# ebox.net
KiCad netlist of a schematic drawn in EAGLE
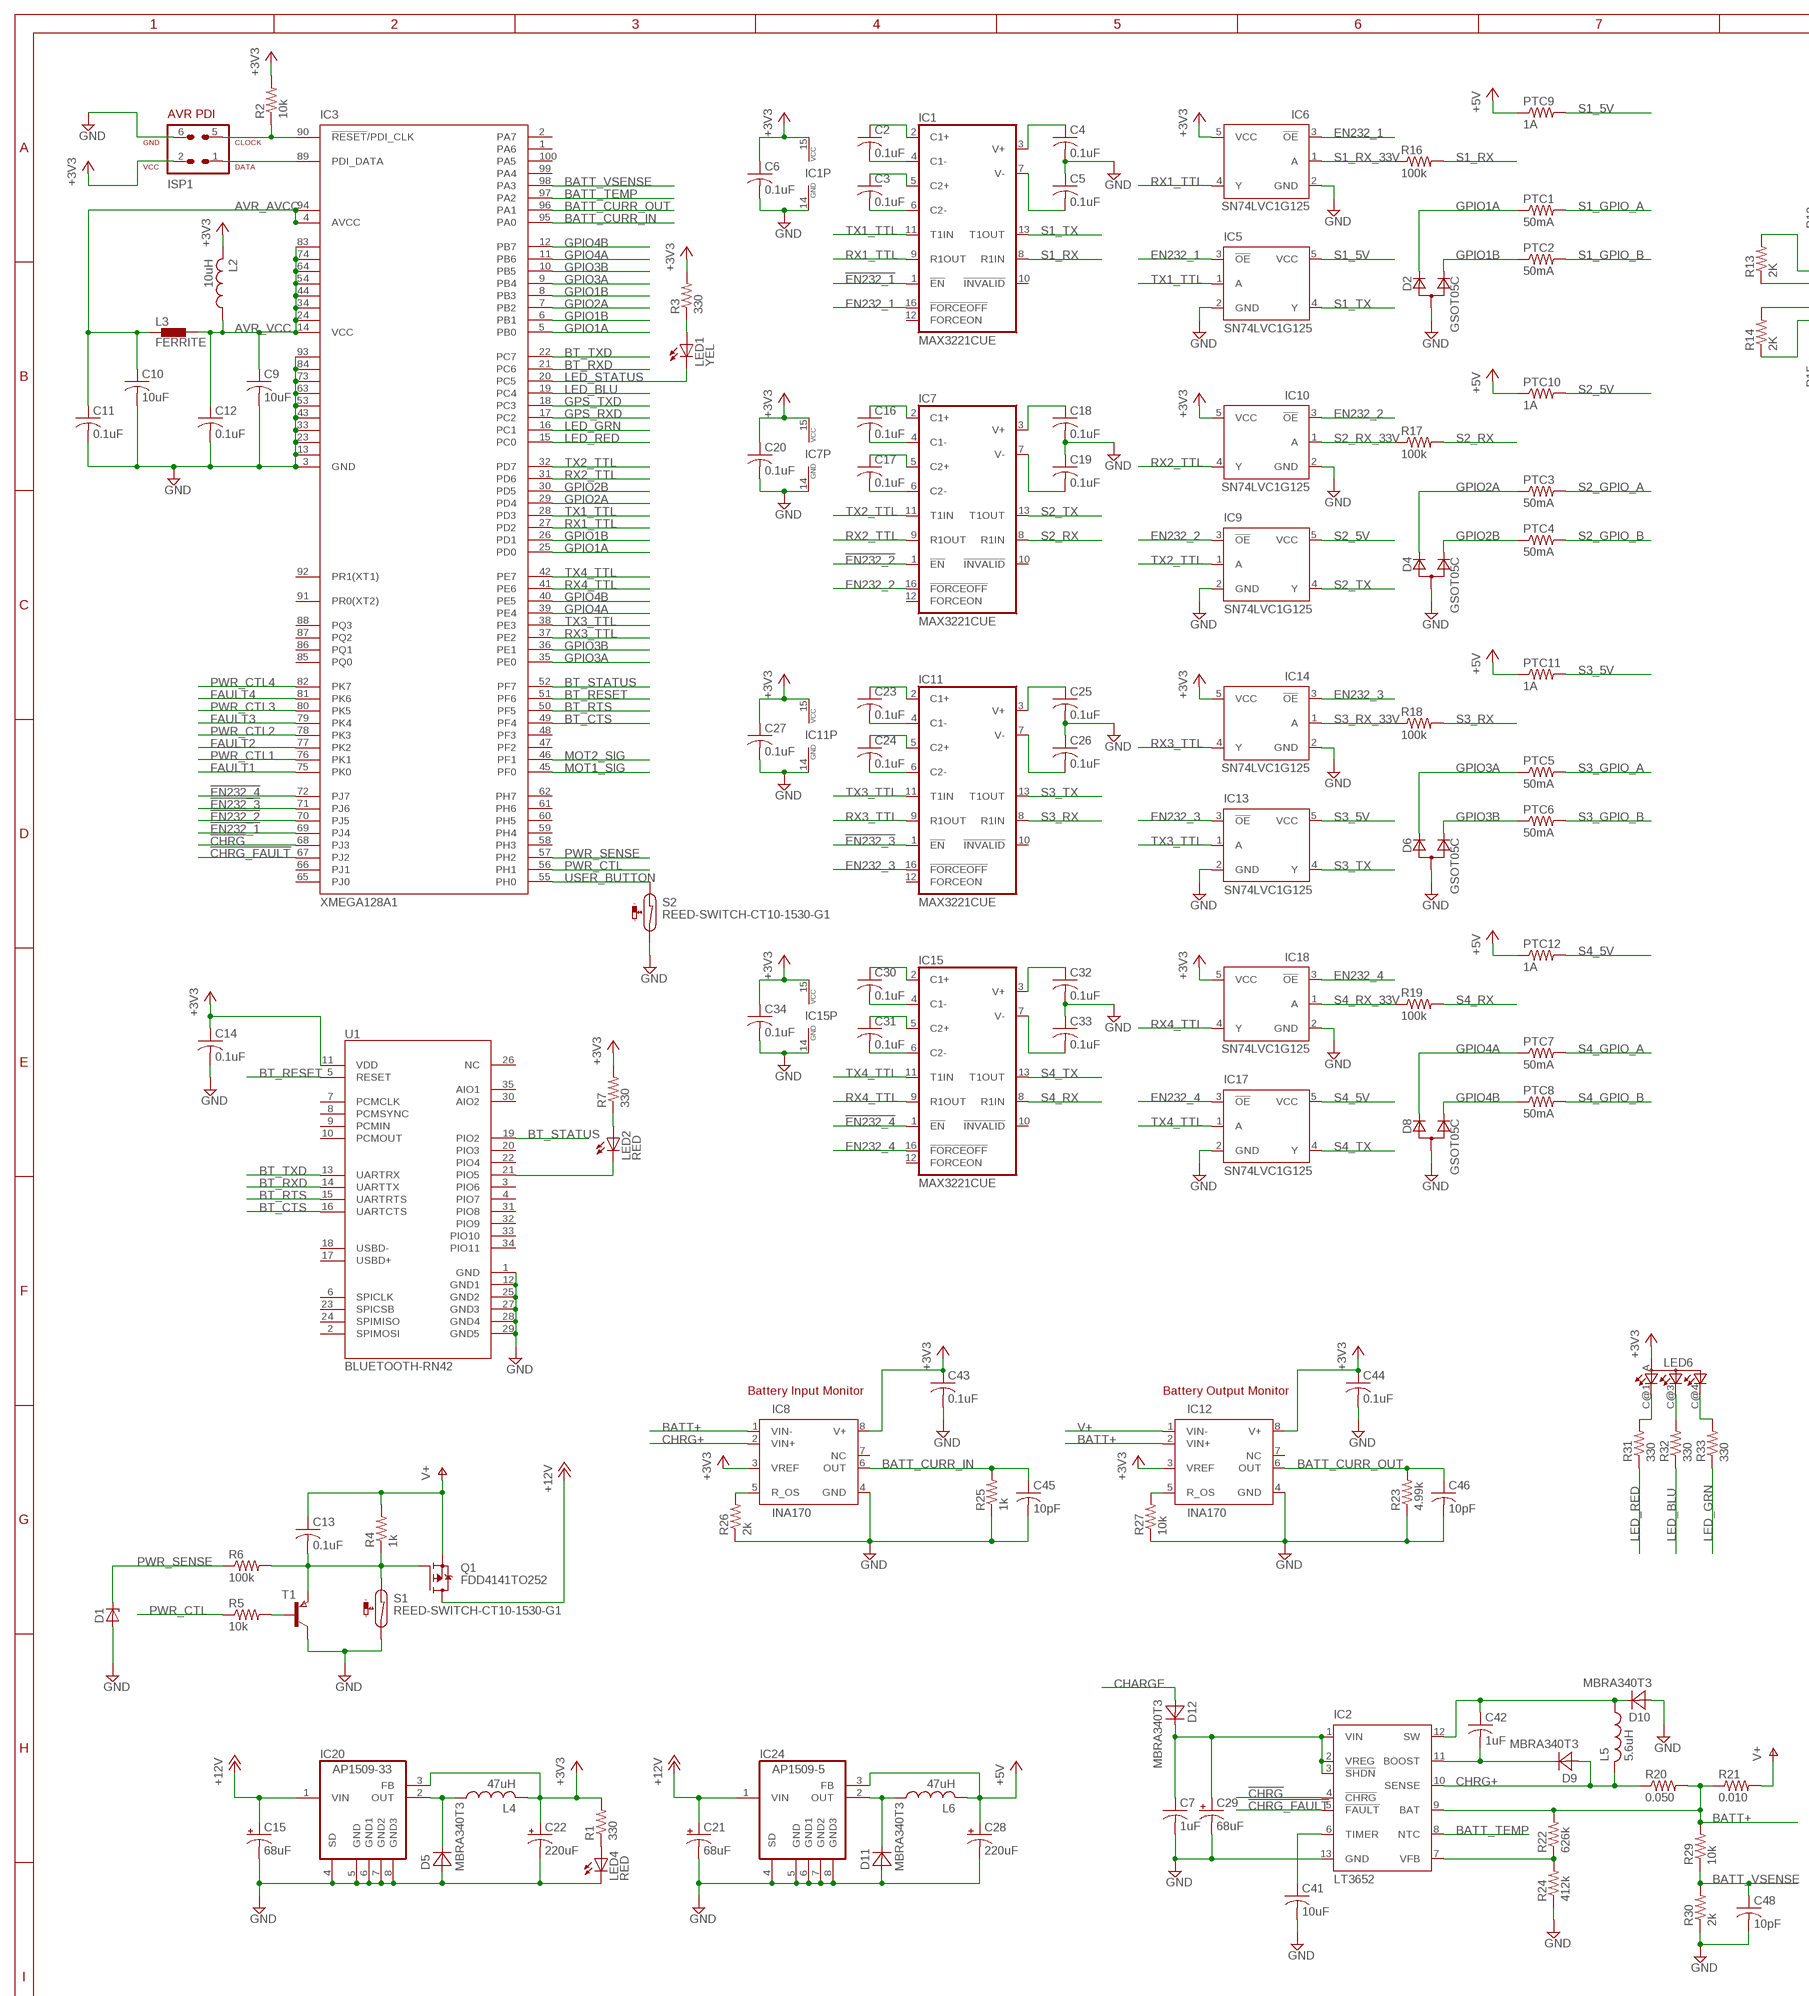
[diagram p0: schematic, sheet 1, part 1 of 2]
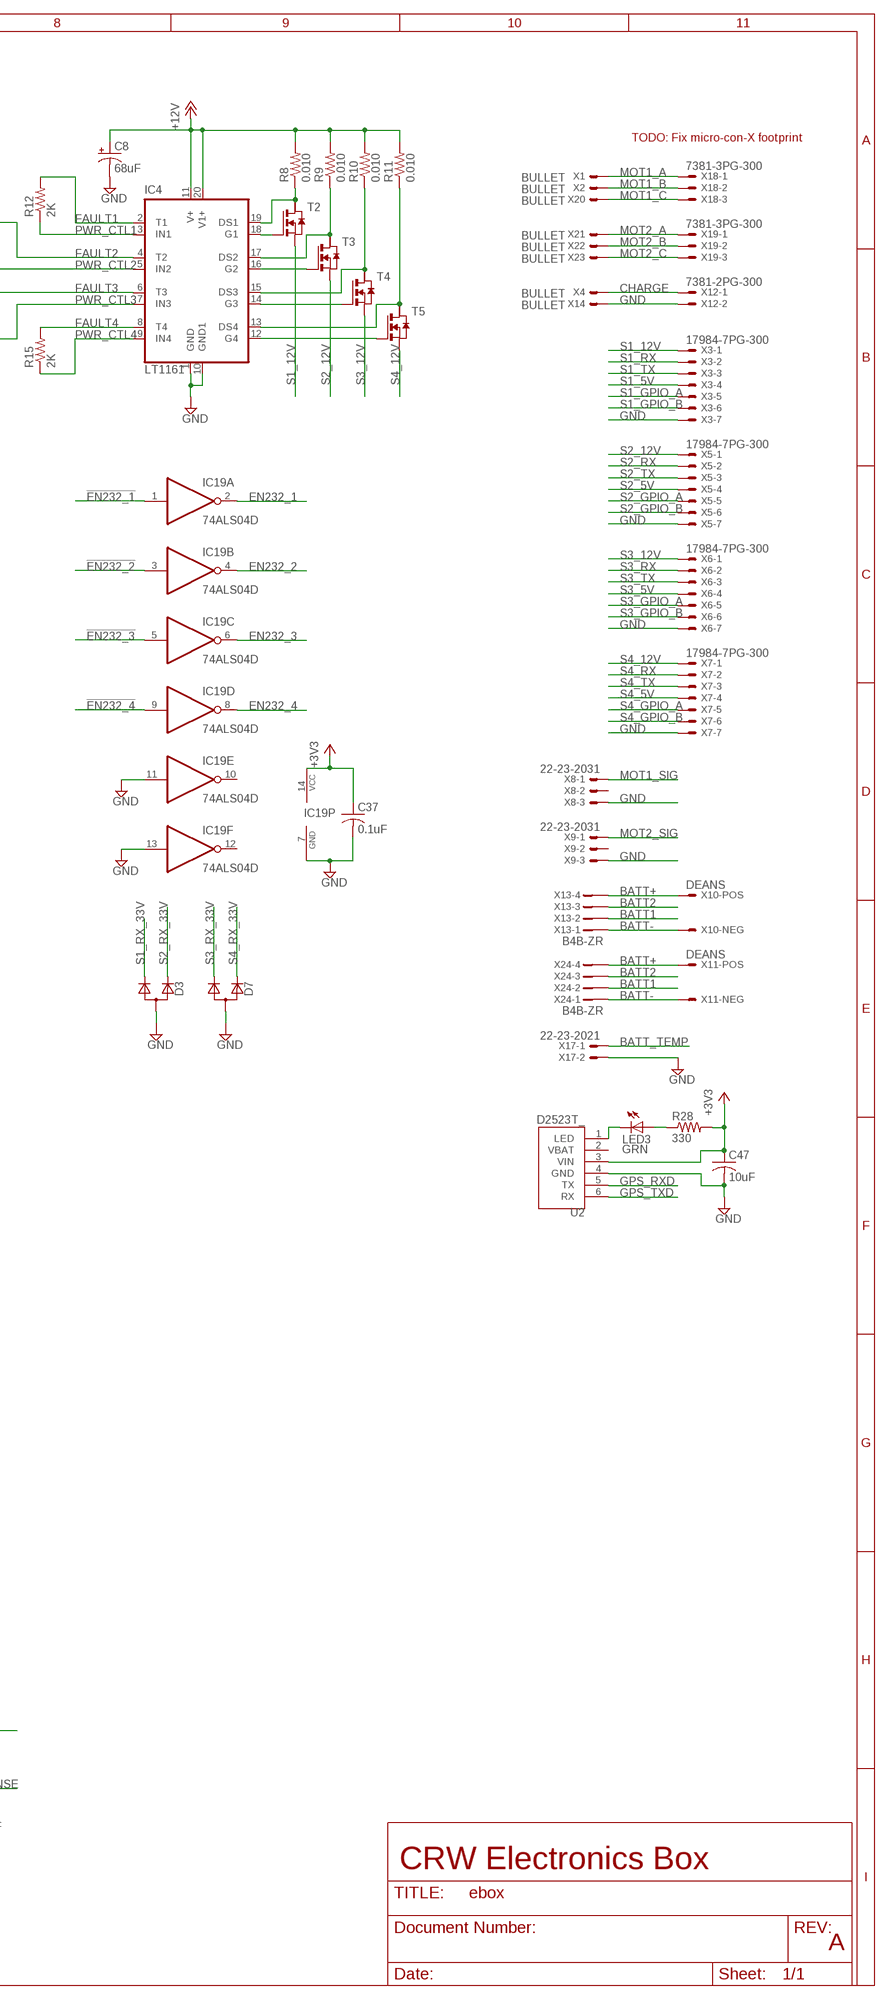
[diagram p1: schematic, sheet 1, part 2 of 2]

(export (version "E")
  (design (tool "Eeschema 10.0.6"))
  (components
    (comp (ref "C2")
      (value "0.1uF")
      (footprint "eagle-import:C0805")
      (libsource (lib "eagle-import") (part "C-USC0805"))
    )
    (comp (ref "C3")
      (value "0.1uF")
      (footprint "eagle-import:C0805")
      (libsource (lib "eagle-import") (part "C-USC0805"))
    )
    (comp (ref "C4")
      (value "0.1uF")
      (footprint "eagle-import:C0805")
      (libsource (lib "eagle-import") (part "C-USC0805"))
    )
    (comp (ref "C5")
      (value "0.1uF")
      (footprint "eagle-import:C0805")
      (libsource (lib "eagle-import") (part "C-USC0805"))
    )
    (comp (ref "C6")
      (value "0.1uF")
      (footprint "eagle-import:C0805")
      (libsource (lib "eagle-import") (part "C-USC0805"))
    )
    (comp (ref "C7")
      (value "1uF")
      (footprint "eagle-import:C0805")
      (libsource (lib "eagle-import") (part "C-USC0805"))
    )
    (comp (ref "C8")
      (value "68uF")
      (footprint "eagle-import:PANASONIC_D")
      (libsource (lib "eagle-import") (part "CPOL-USD"))
    )
    (comp (ref "C9")
      (value "10uF")
      (footprint "eagle-import:C0805")
      (libsource (lib "eagle-import") (part "C-USC0805"))
    )
    (comp (ref "C10")
      (value "10uF")
      (footprint "eagle-import:C0805")
      (libsource (lib "eagle-import") (part "C-USC0805"))
    )
    (comp (ref "C11")
      (value "0.1uF")
      (footprint "eagle-import:C0805")
      (libsource (lib "eagle-import") (part "C-USC0805"))
    )
    (comp (ref "C12")
      (value "0.1uF")
      (footprint "eagle-import:C0805")
      (libsource (lib "eagle-import") (part "C-USC0805"))
    )
    (comp (ref "C13")
      (value "0.1uF")
      (footprint "eagle-import:C0805")
      (libsource (lib "eagle-import") (part "C-USC0805"))
    )
    (comp (ref "C14")
      (value "0.1uF")
      (footprint "eagle-import:C0805")
      (libsource (lib "eagle-import") (part "C-USC0805"))
    )
    (comp (ref "C15")
      (value "68uF")
      (footprint "eagle-import:PANASONIC_D")
      (libsource (lib "eagle-import") (part "CPOL-USD"))
    )
    (comp (ref "C16")
      (value "0.1uF")
      (footprint "eagle-import:C0805")
      (libsource (lib "eagle-import") (part "C-USC0805"))
    )
    (comp (ref "C17")
      (value "0.1uF")
      (footprint "eagle-import:C0805")
      (libsource (lib "eagle-import") (part "C-USC0805"))
    )
    (comp (ref "C18")
      (value "0.1uF")
      (footprint "eagle-import:C0805")
      (libsource (lib "eagle-import") (part "C-USC0805"))
    )
    (comp (ref "C19")
      (value "0.1uF")
      (footprint "eagle-import:C0805")
      (libsource (lib "eagle-import") (part "C-USC0805"))
    )
    (comp (ref "C20")
      (value "0.1uF")
      (footprint "eagle-import:C0805")
      (libsource (lib "eagle-import") (part "C-USC0805"))
    )
    (comp (ref "C21")
      (value "68uF")
      (footprint "eagle-import:PANASONIC_D")
      (libsource (lib "eagle-import") (part "CPOL-USD"))
    )
    (comp (ref "C22")
      (value "220uF")
      (footprint "eagle-import:PANASONIC_D")
      (libsource (lib "eagle-import") (part "CPOL-USD"))
    )
    (comp (ref "C23")
      (value "0.1uF")
      (footprint "eagle-import:C0805")
      (libsource (lib "eagle-import") (part "C-USC0805"))
    )
    (comp (ref "C24")
      (value "0.1uF")
      (footprint "eagle-import:C0805")
      (libsource (lib "eagle-import") (part "C-USC0805"))
    )
    (comp (ref "C25")
      (value "0.1uF")
      (footprint "eagle-import:C0805")
      (libsource (lib "eagle-import") (part "C-USC0805"))
    )
    (comp (ref "C26")
      (value "0.1uF")
      (footprint "eagle-import:C0805")
      (libsource (lib "eagle-import") (part "C-USC0805"))
    )
    (comp (ref "C27")
      (value "0.1uF")
      (footprint "eagle-import:C0805")
      (libsource (lib "eagle-import") (part "C-USC0805"))
    )
    (comp (ref "C28")
      (value "220uF")
      (footprint "eagle-import:PANASONIC_D")
      (libsource (lib "eagle-import") (part "CPOL-USD"))
    )
    (comp (ref "C29")
      (value "68uF")
      (footprint "eagle-import:PANASONIC_D")
      (libsource (lib "eagle-import") (part "CPOL-USD"))
    )
    (comp (ref "C30")
      (value "0.1uF")
      (footprint "eagle-import:C0805")
      (libsource (lib "eagle-import") (part "C-USC0805"))
    )
    (comp (ref "C31")
      (value "0.1uF")
      (footprint "eagle-import:C0805")
      (libsource (lib "eagle-import") (part "C-USC0805"))
    )
    (comp (ref "C32")
      (value "0.1uF")
      (footprint "eagle-import:C0805")
      (libsource (lib "eagle-import") (part "C-USC0805"))
    )
    (comp (ref "C33")
      (value "0.1uF")
      (footprint "eagle-import:C0805")
      (libsource (lib "eagle-import") (part "C-USC0805"))
    )
    (comp (ref "C34")
      (value "0.1uF")
      (footprint "eagle-import:C0805")
      (libsource (lib "eagle-import") (part "C-USC0805"))
    )
    (comp (ref "C37")
      (value "0.1uF")
      (footprint "eagle-import:C0805")
      (libsource (lib "eagle-import") (part "C-USC0805"))
    )
    (comp (ref "C41")
      (value "10uF")
      (footprint "eagle-import:C0805")
      (libsource (lib "eagle-import") (part "C-USC0805"))
    )
    (comp (ref "C42")
      (value "1uF")
      (footprint "eagle-import:C0805")
      (libsource (lib "eagle-import") (part "C-USC0805"))
    )
    (comp (ref "C43")
      (value "0.1uF")
      (footprint "eagle-import:C0805")
      (libsource (lib "eagle-import") (part "C-USC0805"))
    )
    (comp (ref "C44")
      (value "0.1uF")
      (footprint "eagle-import:C0805")
      (libsource (lib "eagle-import") (part "C-USC0805"))
    )
    (comp (ref "C45")
      (value "10pF")
      (footprint "eagle-import:C0805")
      (libsource (lib "eagle-import") (part "C-USC0805"))
    )
    (comp (ref "C46")
      (value "10pF")
      (footprint "eagle-import:C0805")
      (libsource (lib "eagle-import") (part "C-USC0805"))
    )
    (comp (ref "C47")
      (value "10uF")
      (footprint "eagle-import:C0805")
      (libsource (lib "eagle-import") (part "C-USC0805"))
    )
    (comp (ref "C48")
      (value "10pF")
      (footprint "eagle-import:C0805")
      (libsource (lib "eagle-import") (part "C-USC0805"))
    )
    (comp (ref "D1")
      (value "ZENER-DIODESOT23")
      (footprint "eagle-import:SOT23")
      (libsource (lib "eagle-import") (part "ZENER-DIODESOT23"))
    )
    (comp (ref "D2")
      (value "GSOT05C")
      (footprint "eagle-import:SOT-23")
      (libsource (lib "eagle-import") (part "D_2CSOT23"))
    )
    (comp (ref "D3")
      (value "D_2CSOT23")
      (footprint "eagle-import:SOT-23")
      (libsource (lib "eagle-import") (part "D_2CSOT23"))
    )
    (comp (ref "D4")
      (value "GSOT05C")
      (footprint "eagle-import:SOT-23")
      (libsource (lib "eagle-import") (part "D_2CSOT23"))
    )
    (comp (ref "D5")
      (value "MBRA340T3")
      (footprint "eagle-import:SMA")
      (libsource (lib "eagle-import") (part "MBRA340T3"))
    )
    (comp (ref "D6")
      (value "GSOT05C")
      (footprint "eagle-import:SOT-23")
      (libsource (lib "eagle-import") (part "D_2CSOT23"))
    )
    (comp (ref "D7")
      (value "D_2CSOT23")
      (footprint "eagle-import:SOT-23")
      (libsource (lib "eagle-import") (part "D_2CSOT23"))
    )
    (comp (ref "D8")
      (value "GSOT05C")
      (footprint "eagle-import:SOT-23")
      (libsource (lib "eagle-import") (part "D_2CSOT23"))
    )
    (comp (ref "D9")
      (value "MBRA340T3")
      (footprint "eagle-import:SMA")
      (libsource (lib "eagle-import") (part "MBRA340T3"))
    )
    (comp (ref "D10")
      (value "MBRA340T3")
      (footprint "eagle-import:SMA")
      (libsource (lib "eagle-import") (part "MBRA340T3"))
    )
    (comp (ref "D11")
      (value "MBRA340T3")
      (footprint "eagle-import:SMA")
      (libsource (lib "eagle-import") (part "MBRA340T3"))
    )
    (comp (ref "D12")
      (value "MBRA340T3")
      (footprint "eagle-import:SMA")
      (libsource (lib "eagle-import") (part "MBRA340T3"))
    )
    (comp (ref "IC1")
      (value "MAX3221CUE")
      (footprint "eagle-import:TSSOP16")
      (fields (field (name "MF") "MAXIM") (field (name "MPN") "MAX3221CUE+"))
      (libsource (lib "eagle-import") (part "MAX3221UEC"))
    )
    (comp (ref "IC2")
      (value "LT3652")
      (footprint "eagle-import:MSOP12-MSE")
      (fields (field (name "MPN") "AD7992BRMZ-0"))
      (libsource (lib "eagle-import") (part "LT3652"))
    )
    (comp (ref "IC3")
      (value "XMEGA128A1")
      (footprint "eagle-import:TQFP100")
      (libsource (lib "eagle-import") (part "XMEGA128A1"))
    )
    (comp (ref "IC4")
      (value "LT1161")
      (footprint "eagle-import:SOIC20R")
      (libsource (lib "eagle-import") (part "LT1161"))
    )
    (comp (ref "IC5")
      (value "SN74LVC1G125")
      (footprint "eagle-import:SOT23-DBV")
      (libsource (lib "eagle-import") (part "SN74LVC1G125"))
    )
    (comp (ref "IC6")
      (value "SN74LVC1G125")
      (footprint "eagle-import:SOT23-DBV")
      (libsource (lib "eagle-import") (part "SN74LVC1G125"))
    )
    (comp (ref "IC7")
      (value "MAX3221CUE")
      (footprint "eagle-import:TSSOP16")
      (fields (field (name "MF") "MAXIM") (field (name "MPN") "MAX3221CUE+"))
      (libsource (lib "eagle-import") (part "MAX3221UEC"))
    )
    (comp (ref "IC8")
      (value "INA170")
      (footprint "eagle-import:MSOP8")
      (libsource (lib "eagle-import") (part "INA170"))
    )
    (comp (ref "IC9")
      (value "SN74LVC1G125")
      (footprint "eagle-import:SOT23-DBV")
      (libsource (lib "eagle-import") (part "SN74LVC1G125"))
    )
    (comp (ref "IC10")
      (value "SN74LVC1G125")
      (footprint "eagle-import:SOT23-DBV")
      (libsource (lib "eagle-import") (part "SN74LVC1G125"))
    )
    (comp (ref "IC11")
      (value "MAX3221CUE")
      (footprint "eagle-import:TSSOP16")
      (fields (field (name "MF") "MAXIM") (field (name "MPN") "MAX3221CUE+"))
      (libsource (lib "eagle-import") (part "MAX3221UEC"))
    )
    (comp (ref "IC12")
      (value "INA170")
      (footprint "eagle-import:MSOP8")
      (libsource (lib "eagle-import") (part "INA170"))
    )
    (comp (ref "IC13")
      (value "SN74LVC1G125")
      (footprint "eagle-import:SOT23-DBV")
      (libsource (lib "eagle-import") (part "SN74LVC1G125"))
    )
    (comp (ref "IC14")
      (value "SN74LVC1G125")
      (footprint "eagle-import:SOT23-DBV")
      (libsource (lib "eagle-import") (part "SN74LVC1G125"))
    )
    (comp (ref "IC15")
      (value "MAX3221CUE")
      (footprint "eagle-import:TSSOP16")
      (fields (field (name "MF") "MAXIM") (field (name "MPN") "MAX3221CUE+"))
      (libsource (lib "eagle-import") (part "MAX3221UEC"))
    )
    (comp (ref "IC17")
      (value "SN74LVC1G125")
      (footprint "eagle-import:SOT23-DBV")
      (libsource (lib "eagle-import") (part "SN74LVC1G125"))
    )
    (comp (ref "IC18")
      (value "SN74LVC1G125")
      (footprint "eagle-import:SOT23-DBV")
      (libsource (lib "eagle-import") (part "SN74LVC1G125"))
    )
    (comp (ref "IC19")
      (value "74ALS04D")
      (footprint "eagle-import:SO14")
      (libsource (lib "eagle-import") (part "7404DALS"))
    )
    (comp (ref "IC20")
      (value "AP1509-33")
      (footprint "eagle-import:SO08")
      (libsource (lib "eagle-import") (part "AP1509"))
    )
    (comp (ref "IC24")
      (value "AP1509-5")
      (footprint "eagle-import:SO08")
      (libsource (lib "eagle-import") (part "AP1509"))
    )
    (comp (ref "ISP1")
      (value "AVR-PDIVERT")
      (footprint "eagle-import:AVR-ISP-6")
      (libsource (lib "eagle-import") (part "AVR-PDIVERT"))
    )
    (comp (ref "L2")
      (value "10uH")
      (footprint "eagle-import:L2012C")
      (libsource (lib "eagle-import") (part "L-USL2012C"))
    )
    (comp (ref "L3")
      (value "FERRITE")
      (footprint "eagle-import:0402")
      (libsource (lib "eagle-import") (part "BML15HB121SN1"))
    )
    (comp (ref "L4")
      (value "47uH")
      (footprint "eagle-import:L2012C")
      (libsource (lib "eagle-import") (part "L-USL2012C"))
    )
    (comp (ref "L5")
      (value "5.6uH")
      (footprint "eagle-import:L2012C")
      (libsource (lib "eagle-import") (part "L-USL2012C"))
    )
    (comp (ref "L6")
      (value "47uH")
      (footprint "eagle-import:L2012C")
      (libsource (lib "eagle-import") (part "L-USL2012C"))
    )
    (comp (ref "LED1")
      (value "YEL")
      (footprint "eagle-import:CHIPLED_1206")
      (libsource (lib "eagle-import") (part "LEDCHIPLED_1206"))
    )
    (comp (ref "LED2")
      (value "RED")
      (footprint "eagle-import:CHIPLED_1206")
      (libsource (lib "eagle-import") (part "LEDCHIPLED_1206"))
    )
    (comp (ref "LED3")
      (value "GRN")
      (footprint "eagle-import:CHIPLED_1206")
      (libsource (lib "eagle-import") (part "LEDCHIPLED_1206"))
    )
    (comp (ref "LED4")
      (value "RED")
      (footprint "eagle-import:CHIPLED_1206")
      (libsource (lib "eagle-import") (part "LEDCHIPLED_1206"))
    )
    (comp (ref "LED6")
      (value "TOPLED-3P-LCC-4")
      (footprint "eagle-import:P-LCC-4")
      (libsource (lib "eagle-import") (part "TOPLED-3P-LCC-4"))
    )
    (comp (ref "PTC1")
      (value "50mA")
      (footprint "eagle-import:R1206")
      (libsource (lib "eagle-import") (part "R-US_R1206"))
    )
    (comp (ref "PTC2")
      (value "50mA")
      (footprint "eagle-import:R1206")
      (libsource (lib "eagle-import") (part "R-US_R1206"))
    )
    (comp (ref "PTC3")
      (value "50mA")
      (footprint "eagle-import:R1206")
      (libsource (lib "eagle-import") (part "R-US_R1206"))
    )
    (comp (ref "PTC4")
      (value "50mA")
      (footprint "eagle-import:R1206")
      (libsource (lib "eagle-import") (part "R-US_R1206"))
    )
    (comp (ref "PTC5")
      (value "50mA")
      (footprint "eagle-import:R1206")
      (libsource (lib "eagle-import") (part "R-US_R1206"))
    )
    (comp (ref "PTC6")
      (value "50mA")
      (footprint "eagle-import:R1206")
      (libsource (lib "eagle-import") (part "R-US_R1206"))
    )
    (comp (ref "PTC7")
      (value "50mA")
      (footprint "eagle-import:R1206")
      (libsource (lib "eagle-import") (part "R-US_R1206"))
    )
    (comp (ref "PTC8")
      (value "50mA")
      (footprint "eagle-import:R1206")
      (libsource (lib "eagle-import") (part "R-US_R1206"))
    )
    (comp (ref "PTC9")
      (value "1A")
      (footprint "eagle-import:R1206")
      (libsource (lib "eagle-import") (part "R-US_R1206"))
    )
    (comp (ref "PTC10")
      (value "1A")
      (footprint "eagle-import:R1206")
      (libsource (lib "eagle-import") (part "R-US_R1206"))
    )
    (comp (ref "PTC11")
      (value "1A")
      (footprint "eagle-import:R1206")
      (libsource (lib "eagle-import") (part "R-US_R1206"))
    )
    (comp (ref "PTC12")
      (value "1A")
      (footprint "eagle-import:R1206")
      (libsource (lib "eagle-import") (part "R-US_R1206"))
    )
    (comp (ref "Q1")
      (value "FDD4141TO252")
      (footprint "eagle-import:TO252")
      (libsource (lib "eagle-import") (part "FDD4141TO252"))
    )
    (comp (ref "R1")
      (value "330")
      (footprint "eagle-import:R0805")
      (libsource (lib "eagle-import") (part "R-US_R0805"))
    )
    (comp (ref "R2")
      (value "10k")
      (footprint "eagle-import:R0805")
      (libsource (lib "eagle-import") (part "R-US_R0805"))
    )
    (comp (ref "R3")
      (value "330")
      (footprint "eagle-import:R0805")
      (libsource (lib "eagle-import") (part "R-US_R0805"))
    )
    (comp (ref "R4")
      (value "1k")
      (footprint "eagle-import:R0805")
      (libsource (lib "eagle-import") (part "R-US_R0805"))
    )
    (comp (ref "R5")
      (value "10k")
      (footprint "eagle-import:R0805")
      (libsource (lib "eagle-import") (part "R-US_R0805"))
    )
    (comp (ref "R6")
      (value "100k")
      (footprint "eagle-import:R0805")
      (libsource (lib "eagle-import") (part "R-US_R0805"))
    )
    (comp (ref "R7")
      (value "330")
      (footprint "eagle-import:R0805")
      (libsource (lib "eagle-import") (part "R-US_R0805"))
    )
    (comp (ref "R8")
      (value "0.010")
      (footprint "eagle-import:R6332")
      (libsource (lib "eagle-import") (part "R-US_R6332"))
    )
    (comp (ref "R9")
      (value "0.010")
      (footprint "eagle-import:R6332")
      (libsource (lib "eagle-import") (part "R-US_R6332"))
    )
    (comp (ref "R10")
      (value "0.010")
      (footprint "eagle-import:R6332")
      (libsource (lib "eagle-import") (part "R-US_R6332"))
    )
    (comp (ref "R11")
      (value "0.010")
      (footprint "eagle-import:R6332")
      (libsource (lib "eagle-import") (part "R-US_R6332"))
    )
    (comp (ref "R12")
      (value "2K")
      (footprint "eagle-import:R0805")
      (libsource (lib "eagle-import") (part "R-US_R0805"))
    )
    (comp (ref "R13")
      (value "2K")
      (footprint "eagle-import:R0805")
      (libsource (lib "eagle-import") (part "R-US_R0805"))
    )
    (comp (ref "R14")
      (value "2K")
      (footprint "eagle-import:R0805")
      (libsource (lib "eagle-import") (part "R-US_R0805"))
    )
    (comp (ref "R15")
      (value "2K")
      (footprint "eagle-import:R0805")
      (libsource (lib "eagle-import") (part "R-US_R0805"))
    )
    (comp (ref "R16")
      (value "100k")
      (footprint "eagle-import:R0805")
      (libsource (lib "eagle-import") (part "R-US_R0805"))
    )
    (comp (ref "R17")
      (value "100k")
      (footprint "eagle-import:R0805")
      (libsource (lib "eagle-import") (part "R-US_R0805"))
    )
    (comp (ref "R18")
      (value "100k")
      (footprint "eagle-import:R0805")
      (libsource (lib "eagle-import") (part "R-US_R0805"))
    )
    (comp (ref "R19")
      (value "100k")
      (footprint "eagle-import:R0805")
      (libsource (lib "eagle-import") (part "R-US_R0805"))
    )
    (comp (ref "R20")
      (value "0.050")
      (footprint "eagle-import:R6332")
      (libsource (lib "eagle-import") (part "R-US_R6332"))
    )
    (comp (ref "R21")
      (value "0.010")
      (footprint "eagle-import:R6332")
      (libsource (lib "eagle-import") (part "R-US_R6332"))
    )
    (comp (ref "R22")
      (value "626k")
      (footprint "eagle-import:R0805")
      (libsource (lib "eagle-import") (part "R-US_R0805"))
    )
    (comp (ref "R23")
      (value "4.99k")
      (footprint "eagle-import:R0805")
      (libsource (lib "eagle-import") (part "R-US_R0805"))
    )
    (comp (ref "R24")
      (value "412k")
      (footprint "eagle-import:R0805")
      (libsource (lib "eagle-import") (part "R-US_R0805"))
    )
    (comp (ref "R25")
      (value "1k")
      (footprint "eagle-import:R0805")
      (libsource (lib "eagle-import") (part "R-US_R0805"))
    )
    (comp (ref "R26")
      (value "2k")
      (footprint "eagle-import:R0805")
      (libsource (lib "eagle-import") (part "R-US_R0805"))
    )
    (comp (ref "R27")
      (value "10k")
      (footprint "eagle-import:R0805")
      (libsource (lib "eagle-import") (part "R-US_R0805"))
    )
    (comp (ref "R28")
      (value "330")
      (footprint "eagle-import:R0805")
      (libsource (lib "eagle-import") (part "R-US_R0805"))
    )
    (comp (ref "R29")
      (value "10k")
      (footprint "eagle-import:R0805")
      (libsource (lib "eagle-import") (part "R-US_R0805"))
    )
    (comp (ref "R30")
      (value "2k")
      (footprint "eagle-import:R0805")
      (libsource (lib "eagle-import") (part "R-US_R0805"))
    )
    (comp (ref "R31")
      (value "330")
      (footprint "eagle-import:R0805")
      (libsource (lib "eagle-import") (part "R-US_R0805"))
    )
    (comp (ref "R32")
      (value "330")
      (footprint "eagle-import:R0805")
      (libsource (lib "eagle-import") (part "R-US_R0805"))
    )
    (comp (ref "R33")
      (value "330")
      (footprint "eagle-import:R0805")
      (libsource (lib "eagle-import") (part "R-US_R0805"))
    )
    (comp (ref "S1")
      (value "REED-SWITCH-CT10-1530-G1")
      (footprint "eagle-import:CT10-G1")
      (fields (field (name "MF") "COTO TECHNOLOGY") (field (name "MPN") "CT10-1530-G1"))
      (libsource (lib "eagle-import") (part "REED-SWITCH-CT10-1530-G1"))
    )
    (comp (ref "S2")
      (value "REED-SWITCH-CT10-1530-G1")
      (footprint "eagle-import:CT10-G1")
      (fields (field (name "MF") "COTO TECHNOLOGY") (field (name "MPN") "CT10-1530-G1"))
      (libsource (lib "eagle-import") (part "REED-SWITCH-CT10-1530-G1"))
    )
    (comp (ref "T1")
      (value "PNPSOT23")
      (footprint "eagle-import:SOT-23")
      (fields (field (name "MPN") "DSS20200L-7"))
      (libsource (lib "eagle-import") (part "PNPSOT23"))
    )
    (comp (ref "T2")
      (value "NMOSSOT223")
      (footprint "eagle-import:SOT223")
      (libsource (lib "eagle-import") (part "NMOSSOT223"))
    )
    (comp (ref "T3")
      (value "NMOSSOT223")
      (footprint "eagle-import:SOT223")
      (libsource (lib "eagle-import") (part "NMOSSOT223"))
    )
    (comp (ref "T4")
      (value "NMOSSOT223")
      (footprint "eagle-import:SOT223")
      (libsource (lib "eagle-import") (part "NMOSSOT223"))
    )
    (comp (ref "T5")
      (value "NMOSSOT223")
      (footprint "eagle-import:SOT223")
      (libsource (lib "eagle-import") (part "NMOSSOT223"))
    )
    (comp (ref "U1")
      (value "BLUETOOTH-RN42")
      (footprint "eagle-import:RN41")
      (libsource (lib "eagle-import") (part "BLUETOOTH-RN41{dblquote}"))
    )
    (comp (ref "U2")
      (value "D2523T_")
      (footprint "eagle-import:EM406")
      (libsource (lib "eagle-import") (part "D2523T_"))
    )
    (comp (ref "X1")
      (value "BULLET")
      (footprint "eagle-import:BULLET")
      (libsource (lib "eagle-import") (part "BULLET"))
    )
    (comp (ref "X2")
      (value "BULLET")
      (footprint "eagle-import:BULLET")
      (libsource (lib "eagle-import") (part "BULLET"))
    )
    (comp (ref "X3")
      (value "17984-7PG-300")
      (footprint "eagle-import:17984-7PG-300")
      (libsource (lib "eagle-import") (part "17984-7PG-300"))
    )
    (comp (ref "X4")
      (value "BULLET")
      (footprint "eagle-import:BULLET")
      (libsource (lib "eagle-import") (part "BULLET"))
    )
    (comp (ref "X5")
      (value "17984-7PG-300")
      (footprint "eagle-import:17984-7PG-300")
      (libsource (lib "eagle-import") (part "17984-7PG-300"))
    )
    (comp (ref "X6")
      (value "17984-7PG-300")
      (footprint "eagle-import:17984-7PG-300")
      (libsource (lib "eagle-import") (part "17984-7PG-300"))
    )
    (comp (ref "X7")
      (value "17984-7PG-300")
      (footprint "eagle-import:17984-7PG-300")
      (libsource (lib "eagle-import") (part "17984-7PG-300"))
    )
    (comp (ref "X8")
      (value "22-23-2031")
      (footprint "eagle-import:22-23-2031")
      (fields (field (name "MF") "MOLEX"))
      (libsource (lib "eagle-import") (part "22-23-2031"))
    )
    (comp (ref "X9")
      (value "22-23-2031")
      (footprint "eagle-import:22-23-2031")
      (fields (field (name "MF") "MOLEX"))
      (libsource (lib "eagle-import") (part "22-23-2031"))
    )
    (comp (ref "X10")
      (value "DEANS")
      (footprint "eagle-import:DEANS")
      (libsource (lib "eagle-import") (part "DEANS"))
    )
    (comp (ref "X11")
      (value "DEANS")
      (footprint "eagle-import:DEANS")
      (libsource (lib "eagle-import") (part "DEANS"))
    )
    (comp (ref "X12")
      (value "7381-2PG-300")
      (footprint "eagle-import:7381-2PG-300")
      (libsource (lib "eagle-import") (part "7381-2PG-300"))
    )
    (comp (ref "X13")
      (value "B4B-ZR")
      (footprint "eagle-import:B4B-ZR")
      (fields (field (name "MF") "FARNELL") (field (name "MPN") "B4B-ZR(LF)(SN)"))
      (libsource (lib "eagle-import") (part "?4B-ZRB"))
    )
    (comp (ref "X14")
      (value "BULLET")
      (footprint "eagle-import:BULLET")
      (libsource (lib "eagle-import") (part "BULLET"))
    )
    (comp (ref "X17")
      (value "22-23-2021")
      (footprint "eagle-import:22-23-2021")
      (fields (field (name "MF") "MOLEX"))
      (libsource (lib "eagle-import") (part "22-23-2021"))
    )
    (comp (ref "X18")
      (value "7381-3PG-300")
      (footprint "eagle-import:7381-3PG-300")
      (libsource (lib "eagle-import") (part "7381-3PG-300"))
    )
    (comp (ref "X19")
      (value "7381-3PG-300")
      (footprint "eagle-import:7381-3PG-300")
      (libsource (lib "eagle-import") (part "7381-3PG-300"))
    )
    (comp (ref "X20")
      (value "BULLET")
      (footprint "eagle-import:BULLET")
      (libsource (lib "eagle-import") (part "BULLET"))
    )
    (comp (ref "X21")
      (value "BULLET")
      (footprint "eagle-import:BULLET")
      (libsource (lib "eagle-import") (part "BULLET"))
    )
    (comp (ref "X22")
      (value "BULLET")
      (footprint "eagle-import:BULLET")
      (libsource (lib "eagle-import") (part "BULLET"))
    )
    (comp (ref "X23")
      (value "BULLET")
      (footprint "eagle-import:BULLET")
      (libsource (lib "eagle-import") (part "BULLET"))
    )
    (comp (ref "X24")
      (value "B4B-ZR")
      (footprint "eagle-import:B4B-ZR")
      (fields (field (name "MF") "FARNELL") (field (name "MPN") "B4B-ZR(LF)(SN)"))
      (libsource (lib "eagle-import") (part "?4B-ZRB"))
    )
  )
  (nets
    (net (code "1") (name "+3V3") (class "Default")
      (node (ref "C14") (pin "1") (pinfunction "1_1") (pintype "passive"))
      (node (ref "C20") (pin "1") (pinfunction "1_1") (pintype "passive"))
      (node (ref "C22") (pin "+") (pinfunction "+_+") (pintype "passive"))
      (node (ref "C27") (pin "1") (pinfunction "1_1") (pintype "passive"))
      (node (ref "C34") (pin "1") (pinfunction "1_1") (pintype "passive"))
      (node (ref "C37") (pin "1") (pinfunction "1_1") (pintype "passive"))
      (node (ref "C43") (pin "1") (pinfunction "1_1") (pintype "passive"))
      (node (ref "C44") (pin "1") (pinfunction "1_1") (pintype "passive"))
      (node (ref "C47") (pin "1") (pinfunction "1_1") (pintype "passive"))
      (node (ref "C6") (pin "1") (pinfunction "1_1") (pintype "passive"))
      (node (ref "IC1") (pin "15") (pinfunction "VCC_15") (pintype "power_in"))
      (node (ref "IC10") (pin "5") (pinfunction "VCC_5") (pintype "passive"))
      (node (ref "IC11") (pin "15") (pinfunction "VCC_15") (pintype "power_in"))
      (node (ref "IC12") (pin "3") (pinfunction "VREF_3") (pintype "input"))
      (node (ref "IC12") (pin "8") (pinfunction "V+_8") (pintype "input"))
      (node (ref "IC14") (pin "5") (pinfunction "VCC_5") (pintype "passive"))
      (node (ref "IC15") (pin "15") (pinfunction "VCC_15") (pintype "power_in"))
      (node (ref "IC18") (pin "5") (pinfunction "VCC_5") (pintype "passive"))
      (node (ref "IC19") (pin "14") (pinfunction "VCC_14") (pintype "power_in"))
      (node (ref "IC20") (pin "3") (pinfunction "FB_3") (pintype "output"))
      (node (ref "IC6") (pin "5") (pinfunction "VCC_5") (pintype "passive"))
      (node (ref "IC7") (pin "15") (pinfunction "VCC_15") (pintype "power_in"))
      (node (ref "IC8") (pin "3") (pinfunction "VREF_3") (pintype "input"))
      (node (ref "IC8") (pin "8") (pinfunction "V+_8") (pintype "input"))
      (node (ref "ISP1") (pin "2") (pinfunction "2_2") (pintype "passive"))
      (node (ref "L2") (pin "2") (pinfunction "2_2") (pintype "passive"))
      (node (ref "L4") (pin "2") (pinfunction "2_2") (pintype "passive"))
      (node (ref "LED6") (pin "A") (pinfunction "A2_A") (pintype "passive"))
      (node (ref "R1") (pin "2") (pinfunction "2_2") (pintype "passive"))
      (node (ref "R2") (pin "2") (pinfunction "2_2") (pintype "passive"))
      (node (ref "R28") (pin "2") (pinfunction "2_2") (pintype "passive"))
      (node (ref "R3") (pin "2") (pinfunction "2_2") (pintype "passive"))
      (node (ref "R7") (pin "2") (pinfunction "2_2") (pintype "passive"))
      (node (ref "U1") (pin "11") (pinfunction "VDD_11") (pintype "bidirectional"))
      (node (ref "U2") (pin "3") (pinfunction "VIN_3") (pintype "bidirectional"))
    )
    (net (code "2") (name "+5V") (class "Default")
      (node (ref "C28") (pin "+") (pinfunction "+_+") (pintype "passive"))
      (node (ref "IC24") (pin "3") (pinfunction "FB_3") (pintype "output"))
      (node (ref "L6") (pin "2") (pinfunction "2_2") (pintype "passive"))
      (node (ref "PTC10") (pin "1") (pinfunction "1_1") (pintype "passive"))
      (node (ref "PTC11") (pin "1") (pinfunction "1_1") (pintype "passive"))
      (node (ref "PTC12") (pin "1") (pinfunction "1_1") (pintype "passive"))
      (node (ref "PTC9") (pin "1") (pinfunction "1_1") (pintype "passive"))
    )
    (net (code "3") (name "+12V") (class "Default")
      (node (ref "C15") (pin "+") (pinfunction "+_+") (pintype "passive"))
      (node (ref "C21") (pin "+") (pinfunction "+_+") (pintype "passive"))
      (node (ref "C8") (pin "+") (pinfunction "+_+") (pintype "passive"))
      (node (ref "IC20") (pin "1") (pinfunction "VIN_1") (pintype "input"))
      (node (ref "IC24") (pin "1") (pinfunction "VIN_1") (pintype "input"))
      (node (ref "IC4") (pin "11") (pinfunction "V+_11") (pintype "input"))
      (node (ref "IC4") (pin "20") (pinfunction "V1+_20") (pintype "input"))
      (node (ref "Q1") (pin "3") (pinfunction "D_3") (pintype "passive"))
      (node (ref "R10") (pin "2") (pinfunction "2_2") (pintype "passive"))
      (node (ref "R11") (pin "2") (pinfunction "2_2") (pintype "passive"))
      (node (ref "R8") (pin "2") (pinfunction "2_2") (pintype "passive"))
      (node (ref "R9") (pin "2") (pinfunction "2_2") (pintype "passive"))
    )
    (net (code "4") (name "/AVR_AVCC") (class "Default")
      (node (ref "C10") (pin "1") (pinfunction "1_1") (pintype "passive"))
      (node (ref "C11") (pin "1") (pinfunction "1_1") (pintype "passive"))
      (node (ref "IC3") (pin "4") (pinfunction "AVCC_4") (pintype "power_in"))
      (node (ref "IC3") (pin "94") (pinfunction "AVCC1_94") (pintype "power_in"))
      (node (ref "L3") (pin "1") (pinfunction "1_1") (pintype "passive"))
    )
    (net (code "5") (name "/AVR_VCC") (class "Default")
      (node (ref "C12") (pin "1") (pinfunction "1_1") (pintype "passive"))
      (node (ref "C9") (pin "1") (pinfunction "1_1") (pintype "passive"))
      (node (ref "IC3") (pin "14") (pinfunction "VCC_14") (pintype "power_in"))
      (node (ref "IC3") (pin "24") (pinfunction "VCC1_24") (pintype "power_in"))
      (node (ref "IC3") (pin "34") (pinfunction "VCC2_34") (pintype "power_in"))
      (node (ref "IC3") (pin "44") (pinfunction "VCC3_44") (pintype "power_in"))
      (node (ref "IC3") (pin "54") (pinfunction "VCC4_54") (pintype "power_in"))
      (node (ref "IC3") (pin "64") (pinfunction "VCC5_64") (pintype "power_in"))
      (node (ref "IC3") (pin "74") (pinfunction "VCC6_74") (pintype "power_in"))
      (node (ref "IC3") (pin "83") (pinfunction "VCC7_83") (pintype "power_in"))
      (node (ref "L2") (pin "1") (pinfunction "1_1") (pintype "passive"))
      (node (ref "L3") (pin "2") (pinfunction "2_2") (pintype "passive"))
    )
    (net (code "6") (name "/BATT+") (class "Default")
      (node (ref "IC12") (pin "2") (pinfunction "VIN+_2") (pintype "passive"))
      (node (ref "IC2") (pin "9") (pinfunction "BAT_9") (pintype "input"))
      (node (ref "IC8") (pin "1") (pinfunction "VIN-_1") (pintype "passive"))
      (node (ref "R20") (pin "2") (pinfunction "2_2") (pintype "passive"))
      (node (ref "R21") (pin "1") (pinfunction "1_1") (pintype "passive"))
      (node (ref "R22") (pin "2") (pinfunction "2_2") (pintype "passive"))
      (node (ref "R29") (pin "2") (pinfunction "2_2") (pintype "passive"))
      (node (ref "X10") (pin "POS") (pinfunction "S_POS") (pintype "passive"))
      (node (ref "X11") (pin "POS") (pinfunction "S_POS") (pintype "passive"))
      (node (ref "X13") (pin "4") (pinfunction "1_4") (pintype "passive"))
      (node (ref "X24") (pin "4") (pinfunction "1_4") (pintype "passive"))
    )
    (net (code "7") (name "/BATT-") (class "Default")
      (node (ref "X10") (pin "NEG") (pinfunction "S_NEG") (pintype "passive"))
      (node (ref "X11") (pin "NEG") (pinfunction "S_NEG") (pintype "passive"))
      (node (ref "X13") (pin "1") (pinfunction "1_1") (pintype "passive"))
      (node (ref "X24") (pin "1") (pinfunction "1_1") (pintype "passive"))
    )
    (net (code "8") (name "/BATT1") (class "Default")
      (node (ref "X13") (pin "2") (pinfunction "1_2") (pintype "passive"))
      (node (ref "X24") (pin "2") (pinfunction "1_2") (pintype "passive"))
    )
    (net (code "9") (name "/BATT2") (class "Default")
      (node (ref "X13") (pin "3") (pinfunction "1_3") (pintype "passive"))
      (node (ref "X24") (pin "3") (pinfunction "1_3") (pintype "passive"))
    )
    (net (code "10") (name "/BATT_CURR_IN") (class "Default")
      (node (ref "C45") (pin "1") (pinfunction "1_1") (pintype "passive"))
      (node (ref "IC3") (pin "95") (pinfunction "PA0_95") (pintype "bidirectional"))
      (node (ref "IC8") (pin "6") (pinfunction "OUT_6") (pintype "passive"))
      (node (ref "R25") (pin "2") (pinfunction "2_2") (pintype "passive"))
    )
    (net (code "11") (name "/BATT_CURR_OUT") (class "Default")
      (node (ref "C46") (pin "1") (pinfunction "1_1") (pintype "passive"))
      (node (ref "IC12") (pin "6") (pinfunction "OUT_6") (pintype "passive"))
      (node (ref "IC3") (pin "96") (pinfunction "PA1_96") (pintype "bidirectional"))
      (node (ref "R23") (pin "2") (pinfunction "2_2") (pintype "passive"))
    )
    (net (code "12") (name "/BATT_TEMP") (class "Default")
      (node (ref "IC2") (pin "8") (pinfunction "NTC_8") (pintype "bidirectional"))
      (node (ref "IC3") (pin "97") (pinfunction "PA2_97") (pintype "bidirectional"))
      (node (ref "X17") (pin "1") (pinfunction "S_1") (pintype "passive"))
    )
    (net (code "13") (name "/BATT_VSENSE") (class "Default")
      (node (ref "C48") (pin "1") (pinfunction "1_1") (pintype "passive"))
      (node (ref "IC3") (pin "98") (pinfunction "PA3_98") (pintype "bidirectional"))
      (node (ref "R29") (pin "1") (pinfunction "1_1") (pintype "passive"))
      (node (ref "R30") (pin "2") (pinfunction "2_2") (pintype "passive"))
    )
    (net (code "14") (name "/BT_CTS") (class "Default")
      (node (ref "IC3") (pin "49") (pinfunction "PF4_49") (pintype "bidirectional"))
      (node (ref "U1") (pin "16") (pinfunction "UARTCTS_16") (pintype "bidirectional"))
    )
    (net (code "15") (name "/BT_RESET") (class "Default")
      (node (ref "IC3") (pin "51") (pinfunction "PF6_51") (pintype "bidirectional"))
      (node (ref "U1") (pin "5") (pinfunction "RESET_5") (pintype "bidirectional"))
    )
    (net (code "16") (name "/BT_RTS") (class "Default")
      (node (ref "IC3") (pin "50") (pinfunction "PF5_50") (pintype "bidirectional"))
      (node (ref "U1") (pin "15") (pinfunction "UARTRTS_15") (pintype "bidirectional"))
    )
    (net (code "17") (name "/BT_RXD") (class "Default")
      (node (ref "IC3") (pin "21") (pinfunction "PC6_21") (pintype "bidirectional"))
      (node (ref "U1") (pin "14") (pinfunction "UARTTX_14") (pintype "bidirectional"))
    )
    (net (code "18") (name "/BT_STATUS") (class "Default")
      (node (ref "IC3") (pin "52") (pinfunction "PF7_52") (pintype "bidirectional"))
      (node (ref "U1") (pin "19") (pinfunction "PIO2_19") (pintype "bidirectional"))
    )
    (net (code "19") (name "/BT_TXD") (class "Default")
      (node (ref "IC3") (pin "22") (pinfunction "PC7_22") (pintype "bidirectional"))
      (node (ref "U1") (pin "13") (pinfunction "UARTRX_13") (pintype "bidirectional"))
    )
    (net (code "20") (name "/CHARGE") (class "Default")
      (node (ref "D12") (pin "A") (pinfunction "A_A") (pintype "passive"))
      (node (ref "X12") (pin "1") (pinfunction "S_1") (pintype "passive"))
      (node (ref "X4") (pin "P$1") (pinfunction "S_P$1") (pintype "passive"))
    )
    (net (code "21") (name "/CHRG+") (class "Default")
      (node (ref "D9") (pin "A") (pinfunction "A_A") (pintype "passive"))
      (node (ref "IC2") (pin "10") (pinfunction "SENSE_10") (pintype "input"))
      (node (ref "IC8") (pin "2") (pinfunction "VIN+_2") (pintype "passive"))
      (node (ref "L5") (pin "2") (pinfunction "2_2") (pintype "passive"))
      (node (ref "R20") (pin "1") (pinfunction "1_1") (pintype "passive"))
    )
    (net (code "22") (name "/EN232_1") (class "Default")
      (node (ref "IC1") (pin "16") (pinfunction "~{FORCEOFF}_16") (pintype "input"))
      (node (ref "IC19") (pin "2") (pinfunction "O_2") (pintype "output"))
      (node (ref "IC5") (pin "3") (pinfunction "~{OE}_3") (pintype "input"))
      (node (ref "IC6") (pin "3") (pinfunction "~{OE}_3") (pintype "input"))
    )
    (net (code "23") (name "/EN232_2") (class "Default")
      (node (ref "IC10") (pin "3") (pinfunction "~{OE}_3") (pintype "input"))
      (node (ref "IC19") (pin "4") (pinfunction "O_4") (pintype "output"))
      (node (ref "IC7") (pin "16") (pinfunction "~{FORCEOFF}_16") (pintype "input"))
      (node (ref "IC9") (pin "3") (pinfunction "~{OE}_3") (pintype "input"))
    )
    (net (code "24") (name "/EN232_3") (class "Default")
      (node (ref "IC11") (pin "16") (pinfunction "~{FORCEOFF}_16") (pintype "input"))
      (node (ref "IC13") (pin "3") (pinfunction "~{OE}_3") (pintype "input"))
      (node (ref "IC14") (pin "3") (pinfunction "~{OE}_3") (pintype "input"))
      (node (ref "IC19") (pin "6") (pinfunction "O_6") (pintype "output"))
    )
    (net (code "25") (name "/EN232_4") (class "Default")
      (node (ref "IC15") (pin "16") (pinfunction "~{FORCEOFF}_16") (pintype "input"))
      (node (ref "IC17") (pin "3") (pinfunction "~{OE}_3") (pintype "input"))
      (node (ref "IC18") (pin "3") (pinfunction "~{OE}_3") (pintype "input"))
      (node (ref "IC19") (pin "8") (pinfunction "O_8") (pintype "output"))
    )
    (net (code "26") (name "/FAULT1") (class "Default")
      (node (ref "IC3") (pin "75") (pinfunction "PK0_75") (pintype "bidirectional"))
      (node (ref "IC4") (pin "2") (pinfunction "T1_2") (pintype "bidirectional"))
      (node (ref "R12") (pin "2") (pinfunction "2_2") (pintype "passive"))
    )
    (net (code "27") (name "/FAULT2") (class "Default")
      (node (ref "IC3") (pin "77") (pinfunction "PK2_77") (pintype "bidirectional"))
      (node (ref "IC4") (pin "4") (pinfunction "T2_4") (pintype "bidirectional"))
      (node (ref "R13") (pin "2") (pinfunction "2_2") (pintype "passive"))
    )
    (net (code "28") (name "/FAULT3") (class "Default")
      (node (ref "IC3") (pin "79") (pinfunction "PK4_79") (pintype "bidirectional"))
      (node (ref "IC4") (pin "6") (pinfunction "T3_6") (pintype "bidirectional"))
      (node (ref "R14") (pin "2") (pinfunction "2_2") (pintype "passive"))
    )
    (net (code "29") (name "/FAULT4") (class "Default")
      (node (ref "IC3") (pin "81") (pinfunction "PK6_81") (pintype "bidirectional"))
      (node (ref "IC4") (pin "8") (pinfunction "T4_8") (pintype "input"))
      (node (ref "R15") (pin "2") (pinfunction "2_2") (pintype "passive"))
    )
    (net (code "30") (name "/GPIO1A") (class "Default")
      (node (ref "D2") (pin "2") (pinfunction "C1_2") (pintype "passive"))
      (node (ref "IC3") (pin "25") (pinfunction "PD0_25") (pintype "bidirectional"))
      (node (ref "IC3") (pin "5") (pinfunction "PB0_5") (pintype "bidirectional"))
      (node (ref "PTC1") (pin "1") (pinfunction "1_1") (pintype "passive"))
    )
    (net (code "31") (name "/GPIO1B") (class "Default")
      (node (ref "D2") (pin "3") (pinfunction "C2_3") (pintype "passive"))
      (node (ref "IC3") (pin "26") (pinfunction "PD1_26") (pintype "bidirectional"))
      (node (ref "IC3") (pin "6") (pinfunction "PB1_6") (pintype "bidirectional"))
      (node (ref "IC3") (pin "8") (pinfunction "PB3_8") (pintype "bidirectional"))
      (node (ref "PTC2") (pin "1") (pinfunction "1_1") (pintype "passive"))
    )
    (net (code "32") (name "/GPIO2A") (class "Default")
      (node (ref "D4") (pin "2") (pinfunction "C1_2") (pintype "passive"))
      (node (ref "IC3") (pin "29") (pinfunction "PD4_29") (pintype "bidirectional"))
      (node (ref "IC3") (pin "7") (pinfunction "PB2_7") (pintype "bidirectional"))
      (node (ref "PTC3") (pin "1") (pinfunction "1_1") (pintype "passive"))
    )
    (net (code "33") (name "/GPIO2B") (class "Default")
      (node (ref "D4") (pin "3") (pinfunction "C2_3") (pintype "passive"))
      (node (ref "IC3") (pin "30") (pinfunction "PD5_30") (pintype "bidirectional"))
      (node (ref "PTC4") (pin "1") (pinfunction "1_1") (pintype "passive"))
    )
    (net (code "34") (name "/GPIO3A") (class "Default")
      (node (ref "D6") (pin "2") (pinfunction "C1_2") (pintype "passive"))
      (node (ref "IC3") (pin "35") (pinfunction "PE0_35") (pintype "bidirectional"))
      (node (ref "IC3") (pin "9") (pinfunction "PB4_9") (pintype "bidirectional"))
      (node (ref "PTC5") (pin "1") (pinfunction "1_1") (pintype "passive"))
    )
    (net (code "35") (name "/GPIO3B") (class "Default")
      (node (ref "D6") (pin "3") (pinfunction "C2_3") (pintype "passive"))
      (node (ref "IC3") (pin "10") (pinfunction "PB5_10") (pintype "bidirectional"))
      (node (ref "IC3") (pin "36") (pinfunction "PE1_36") (pintype "bidirectional"))
      (node (ref "PTC6") (pin "1") (pinfunction "1_1") (pintype "passive"))
    )
    (net (code "36") (name "/GPIO4A") (class "Default")
      (node (ref "D8") (pin "2") (pinfunction "C1_2") (pintype "passive"))
      (node (ref "IC3") (pin "11") (pinfunction "PB6_11") (pintype "bidirectional"))
      (node (ref "IC3") (pin "39") (pinfunction "PE4_39") (pintype "bidirectional"))
      (node (ref "PTC7") (pin "1") (pinfunction "1_1") (pintype "passive"))
    )
    (net (code "37") (name "/GPIO4B") (class "Default")
      (node (ref "D8") (pin "3") (pinfunction "C2_3") (pintype "passive"))
      (node (ref "IC3") (pin "12") (pinfunction "PB7_12") (pintype "bidirectional"))
      (node (ref "IC3") (pin "40") (pinfunction "PE5_40") (pintype "bidirectional"))
      (node (ref "PTC8") (pin "1") (pinfunction "1_1") (pintype "passive"))
    )
    (net (code "38") (name "/GPS_RXD") (class "Default")
      (node (ref "IC3") (pin "17") (pinfunction "PC2_17") (pintype "bidirectional"))
      (node (ref "U2") (pin "5") (pinfunction "TX_5") (pintype "bidirectional"))
    )
    (net (code "39") (name "/GPS_TXD") (class "Default")
      (node (ref "IC3") (pin "18") (pinfunction "PC3_18") (pintype "bidirectional"))
      (node (ref "U2") (pin "6") (pinfunction "RX_6") (pintype "bidirectional"))
    )
    (net (code "40") (name "/LED_BLU") (class "Default")
      (node (ref "IC3") (pin "19") (pinfunction "PC4_19") (pintype "bidirectional"))
      (node (ref "R32") (pin "1") (pinfunction "1_1") (pintype "passive"))
    )
    (net (code "41") (name "/LED_GRN") (class "Default")
      (node (ref "IC3") (pin "16") (pinfunction "PC1_16") (pintype "bidirectional"))
      (node (ref "R33") (pin "1") (pinfunction "1_1") (pintype "passive"))
    )
    (net (code "42") (name "/LED_RED") (class "Default")
      (node (ref "IC3") (pin "15") (pinfunction "PC0_15") (pintype "bidirectional"))
      (node (ref "R31") (pin "1") (pinfunction "1_1") (pintype "passive"))
    )
    (net (code "43") (name "/LED_STATUS") (class "Default")
      (node (ref "IC3") (pin "20") (pinfunction "PC5_20") (pintype "bidirectional"))
      (node (ref "LED1") (pin "C") (pinfunction "C_C") (pintype "passive"))
    )
    (net (code "44") (name "/MOT1_A") (class "Default")
      (node (ref "X1") (pin "P$1") (pinfunction "S_P$1") (pintype "passive"))
      (node (ref "X18") (pin "1") (pinfunction "S_1") (pintype "passive"))
    )
    (net (code "45") (name "/MOT1_B") (class "Default")
      (node (ref "X18") (pin "2") (pinfunction "S_2") (pintype "passive"))
      (node (ref "X2") (pin "P$1") (pinfunction "S_P$1") (pintype "passive"))
    )
    (net (code "46") (name "/MOT1_C") (class "Default")
      (node (ref "X18") (pin "3") (pinfunction "S_3") (pintype "passive"))
      (node (ref "X20") (pin "P$1") (pinfunction "S_P$1") (pintype "passive"))
    )
    (net (code "47") (name "/MOT1_SIG") (class "Default")
      (node (ref "IC3") (pin "45") (pinfunction "PF0_45") (pintype "bidirectional"))
      (node (ref "X8") (pin "1") (pinfunction "S_1") (pintype "passive"))
    )
    (net (code "48") (name "/MOT2_A") (class "Default")
      (node (ref "X19") (pin "1") (pinfunction "S_1") (pintype "passive"))
      (node (ref "X21") (pin "P$1") (pinfunction "S_P$1") (pintype "passive"))
    )
    (net (code "49") (name "/MOT2_B") (class "Default")
      (node (ref "X19") (pin "2") (pinfunction "S_2") (pintype "passive"))
      (node (ref "X22") (pin "P$1") (pinfunction "S_P$1") (pintype "passive"))
    )
    (net (code "50") (name "/MOT2_C") (class "Default")
      (node (ref "X19") (pin "3") (pinfunction "S_3") (pintype "passive"))
      (node (ref "X23") (pin "P$1") (pinfunction "S_P$1") (pintype "passive"))
    )
    (net (code "51") (name "/MOT2_SIG") (class "Default")
      (node (ref "IC3") (pin "46") (pinfunction "PF1_46") (pintype "bidirectional"))
      (node (ref "X9") (pin "1") (pinfunction "S_1") (pintype "passive"))
    )
    (net (code "52") (name "/PWR_CTL") (class "Default")
      (node (ref "IC3") (pin "56") (pinfunction "PH1_56") (pintype "bidirectional"))
      (node (ref "R5") (pin "1") (pinfunction "1_1") (pintype "passive"))
    )
    (net (code "53") (name "/PWR_CTL1") (class "Default")
      (node (ref "IC3") (pin "76") (pinfunction "PK1_76") (pintype "bidirectional"))
      (node (ref "IC4") (pin "3") (pinfunction "IN1_3") (pintype "input"))
      (node (ref "R12") (pin "1") (pinfunction "1_1") (pintype "passive"))
    )
    (net (code "54") (name "/PWR_CTL2") (class "Default")
      (node (ref "IC3") (pin "78") (pinfunction "PK3_78") (pintype "bidirectional"))
      (node (ref "IC4") (pin "5") (pinfunction "IN2_5") (pintype "input"))
      (node (ref "R13") (pin "1") (pinfunction "1_1") (pintype "passive"))
    )
    (net (code "55") (name "/PWR_CTL3") (class "Default")
      (node (ref "IC3") (pin "80") (pinfunction "PK5_80") (pintype "bidirectional"))
      (node (ref "IC4") (pin "7") (pinfunction "IN3_7") (pintype "input"))
      (node (ref "R14") (pin "1") (pinfunction "1_1") (pintype "passive"))
    )
    (net (code "56") (name "/PWR_CTL4") (class "Default")
      (node (ref "IC3") (pin "82") (pinfunction "PK7_82") (pintype "bidirectional"))
      (node (ref "IC4") (pin "9") (pinfunction "IN4_9") (pintype "input"))
      (node (ref "R15") (pin "1") (pinfunction "1_1") (pintype "passive"))
    )
    (net (code "57") (name "/PWR_SENSE") (class "Default")
      (node (ref "D1") (pin "3") (pinfunction "C_3") (pintype "passive"))
      (node (ref "IC3") (pin "57") (pinfunction "PH2_57") (pintype "bidirectional"))
      (node (ref "R6") (pin "1") (pinfunction "1_1") (pintype "passive"))
    )
    (net (code "58") (name "/RX1_TTL") (class "Default")
      (node (ref "IC1") (pin "9") (pinfunction "R1OUT_9") (pintype "output"))
      (node (ref "IC3") (pin "27") (pinfunction "PD2_27") (pintype "bidirectional"))
      (node (ref "IC6") (pin "4") (pinfunction "Y_4") (pintype "passive"))
    )
    (net (code "59") (name "/RX2_TTL") (class "Default")
      (node (ref "IC10") (pin "4") (pinfunction "Y_4") (pintype "passive"))
      (node (ref "IC3") (pin "31") (pinfunction "PD6_31") (pintype "bidirectional"))
      (node (ref "IC7") (pin "9") (pinfunction "R1OUT_9") (pintype "output"))
    )
    (net (code "60") (name "/RX3_TTL") (class "Default")
      (node (ref "IC11") (pin "9") (pinfunction "R1OUT_9") (pintype "output"))
      (node (ref "IC14") (pin "4") (pinfunction "Y_4") (pintype "passive"))
      (node (ref "IC3") (pin "37") (pinfunction "PE2_37") (pintype "bidirectional"))
    )
    (net (code "61") (name "/RX4_TTL") (class "Default")
      (node (ref "IC15") (pin "9") (pinfunction "R1OUT_9") (pintype "output"))
      (node (ref "IC18") (pin "4") (pinfunction "Y_4") (pintype "passive"))
      (node (ref "IC3") (pin "41") (pinfunction "PE6_41") (pintype "bidirectional"))
    )
    (net (code "62") (name "/S1_5V") (class "Default")
      (node (ref "IC5") (pin "5") (pinfunction "VCC_5") (pintype "passive"))
      (node (ref "PTC9") (pin "2") (pinfunction "2_2") (pintype "passive"))
      (node (ref "X3") (pin "4") (pinfunction "S_4") (pintype "passive"))
    )
    (net (code "63") (name "/S1_12V") (class "Default")
      (node (ref "T2") (pin "3") (pinfunction "S_3") (pintype "passive"))
      (node (ref "X3") (pin "1") (pinfunction "S_1") (pintype "passive"))
    )
    (net (code "64") (name "/S1_GPIO_A") (class "Default")
      (node (ref "PTC1") (pin "2") (pinfunction "2_2") (pintype "passive"))
      (node (ref "X3") (pin "5") (pinfunction "S_5") (pintype "passive"))
    )
    (net (code "65") (name "/S1_GPIO_B") (class "Default")
      (node (ref "PTC2") (pin "2") (pinfunction "2_2") (pintype "passive"))
      (node (ref "X3") (pin "6") (pinfunction "S_6") (pintype "passive"))
    )
    (net (code "66") (name "/S1_RX") (class "Default")
      (node (ref "IC1") (pin "8") (pinfunction "R1IN_8") (pintype "input"))
      (node (ref "R16") (pin "2") (pinfunction "2_2") (pintype "passive"))
      (node (ref "X3") (pin "2") (pinfunction "S_2") (pintype "passive"))
    )
    (net (code "67") (name "/S1_RX_33V") (class "Default")
      (node (ref "D3") (pin "3") (pinfunction "C2_3") (pintype "passive"))
      (node (ref "IC6") (pin "1") (pinfunction "A_1") (pintype "input"))
      (node (ref "R16") (pin "1") (pinfunction "1_1") (pintype "passive"))
    )
    (net (code "68") (name "/S1_TX") (class "Default")
      (node (ref "IC1") (pin "13") (pinfunction "T1OUT_13") (pintype "output"))
      (node (ref "IC5") (pin "4") (pinfunction "Y_4") (pintype "passive"))
      (node (ref "X3") (pin "3") (pinfunction "S_3") (pintype "passive"))
    )
    (net (code "69") (name "/S2_5V") (class "Default")
      (node (ref "IC9") (pin "5") (pinfunction "VCC_5") (pintype "passive"))
      (node (ref "PTC10") (pin "2") (pinfunction "2_2") (pintype "passive"))
      (node (ref "X5") (pin "4") (pinfunction "S_4") (pintype "passive"))
    )
    (net (code "70") (name "/S2_12V") (class "Default")
      (node (ref "T3") (pin "3") (pinfunction "S_3") (pintype "passive"))
      (node (ref "X5") (pin "1") (pinfunction "S_1") (pintype "passive"))
    )
    (net (code "71") (name "/S2_GPIO_A") (class "Default")
      (node (ref "PTC3") (pin "2") (pinfunction "2_2") (pintype "passive"))
      (node (ref "X5") (pin "5") (pinfunction "S_5") (pintype "passive"))
    )
    (net (code "72") (name "/S2_GPIO_B") (class "Default")
      (node (ref "PTC4") (pin "2") (pinfunction "2_2") (pintype "passive"))
      (node (ref "X5") (pin "6") (pinfunction "S_6") (pintype "passive"))
    )
    (net (code "73") (name "/S2_RX") (class "Default")
      (node (ref "IC7") (pin "8") (pinfunction "R1IN_8") (pintype "input"))
      (node (ref "R17") (pin "2") (pinfunction "2_2") (pintype "passive"))
      (node (ref "X5") (pin "2") (pinfunction "S_2") (pintype "passive"))
    )
    (net (code "74") (name "/S2_RX_33V") (class "Default")
      (node (ref "D3") (pin "2") (pinfunction "C1_2") (pintype "passive"))
      (node (ref "IC10") (pin "1") (pinfunction "A_1") (pintype "input"))
      (node (ref "R17") (pin "1") (pinfunction "1_1") (pintype "passive"))
    )
    (net (code "75") (name "/S2_TX") (class "Default")
      (node (ref "IC7") (pin "13") (pinfunction "T1OUT_13") (pintype "output"))
      (node (ref "IC9") (pin "4") (pinfunction "Y_4") (pintype "passive"))
      (node (ref "X5") (pin "3") (pinfunction "S_3") (pintype "passive"))
    )
    (net (code "76") (name "/S3_5V") (class "Default")
      (node (ref "IC13") (pin "5") (pinfunction "VCC_5") (pintype "passive"))
      (node (ref "PTC11") (pin "2") (pinfunction "2_2") (pintype "passive"))
      (node (ref "X6") (pin "4") (pinfunction "S_4") (pintype "passive"))
    )
    (net (code "77") (name "/S3_12V") (class "Default")
      (node (ref "T4") (pin "3") (pinfunction "S_3") (pintype "passive"))
      (node (ref "X6") (pin "1") (pinfunction "S_1") (pintype "passive"))
    )
    (net (code "78") (name "/S3_GPIO_A") (class "Default")
      (node (ref "PTC5") (pin "2") (pinfunction "2_2") (pintype "passive"))
      (node (ref "X6") (pin "5") (pinfunction "S_5") (pintype "passive"))
    )
    (net (code "79") (name "/S3_GPIO_B") (class "Default")
      (node (ref "PTC6") (pin "2") (pinfunction "2_2") (pintype "passive"))
      (node (ref "X6") (pin "6") (pinfunction "S_6") (pintype "passive"))
    )
    (net (code "80") (name "/S3_RX") (class "Default")
      (node (ref "IC11") (pin "8") (pinfunction "R1IN_8") (pintype "input"))
      (node (ref "R18") (pin "2") (pinfunction "2_2") (pintype "passive"))
      (node (ref "X6") (pin "2") (pinfunction "S_2") (pintype "passive"))
    )
    (net (code "81") (name "/S3_RX_33V") (class "Default")
      (node (ref "D7") (pin "3") (pinfunction "C2_3") (pintype "passive"))
      (node (ref "IC14") (pin "1") (pinfunction "A_1") (pintype "input"))
      (node (ref "R18") (pin "1") (pinfunction "1_1") (pintype "passive"))
    )
    (net (code "82") (name "/S3_TX") (class "Default")
      (node (ref "IC11") (pin "13") (pinfunction "T1OUT_13") (pintype "output"))
      (node (ref "IC13") (pin "4") (pinfunction "Y_4") (pintype "passive"))
      (node (ref "X6") (pin "3") (pinfunction "S_3") (pintype "passive"))
    )
    (net (code "83") (name "/S4_5V") (class "Default")
      (node (ref "IC17") (pin "5") (pinfunction "VCC_5") (pintype "passive"))
      (node (ref "PTC12") (pin "2") (pinfunction "2_2") (pintype "passive"))
      (node (ref "X7") (pin "4") (pinfunction "S_4") (pintype "passive"))
    )
    (net (code "84") (name "/S4_12V") (class "Default")
      (node (ref "T5") (pin "3") (pinfunction "S_3") (pintype "passive"))
      (node (ref "X7") (pin "1") (pinfunction "S_1") (pintype "passive"))
    )
    (net (code "85") (name "/S4_GPIO_A") (class "Default")
      (node (ref "PTC7") (pin "2") (pinfunction "2_2") (pintype "passive"))
      (node (ref "X7") (pin "5") (pinfunction "S_5") (pintype "passive"))
    )
    (net (code "86") (name "/S4_GPIO_B") (class "Default")
      (node (ref "PTC8") (pin "2") (pinfunction "2_2") (pintype "passive"))
      (node (ref "X7") (pin "6") (pinfunction "S_6") (pintype "passive"))
    )
    (net (code "87") (name "/S4_RX") (class "Default")
      (node (ref "IC15") (pin "8") (pinfunction "R1IN_8") (pintype "input"))
      (node (ref "R19") (pin "2") (pinfunction "2_2") (pintype "passive"))
      (node (ref "X7") (pin "2") (pinfunction "S_2") (pintype "passive"))
    )
    (net (code "88") (name "/S4_RX_33V") (class "Default")
      (node (ref "D7") (pin "2") (pinfunction "C1_2") (pintype "passive"))
      (node (ref "IC18") (pin "1") (pinfunction "A_1") (pintype "input"))
      (node (ref "R19") (pin "1") (pinfunction "1_1") (pintype "passive"))
    )
    (net (code "89") (name "/S4_TX") (class "Default")
      (node (ref "IC15") (pin "13") (pinfunction "T1OUT_13") (pintype "output"))
      (node (ref "IC17") (pin "4") (pinfunction "Y_4") (pintype "passive"))
      (node (ref "X7") (pin "3") (pinfunction "S_3") (pintype "passive"))
    )
    (net (code "90") (name "/TX1_TTL") (class "Default")
      (node (ref "IC1") (pin "11") (pinfunction "T1IN_11") (pintype "input"))
      (node (ref "IC3") (pin "28") (pinfunction "PD3_28") (pintype "bidirectional"))
      (node (ref "IC5") (pin "1") (pinfunction "A_1") (pintype "input"))
    )
    (net (code "91") (name "/TX2_TTL") (class "Default")
      (node (ref "IC3") (pin "32") (pinfunction "PD7_32") (pintype "bidirectional"))
      (node (ref "IC7") (pin "11") (pinfunction "T1IN_11") (pintype "input"))
      (node (ref "IC9") (pin "1") (pinfunction "A_1") (pintype "input"))
    )
    (net (code "92") (name "/TX3_TTL") (class "Default")
      (node (ref "IC11") (pin "11") (pinfunction "T1IN_11") (pintype "input"))
      (node (ref "IC13") (pin "1") (pinfunction "A_1") (pintype "input"))
      (node (ref "IC3") (pin "38") (pinfunction "PE3_38") (pintype "bidirectional"))
    )
    (net (code "93") (name "/TX4_TTL") (class "Default")
      (node (ref "IC15") (pin "11") (pinfunction "T1IN_11") (pintype "input"))
      (node (ref "IC17") (pin "1") (pinfunction "A_1") (pintype "input"))
      (node (ref "IC3") (pin "42") (pinfunction "PE7_42") (pintype "bidirectional"))
    )
    (net (code "94") (name "/USER_BUTTON") (class "Default")
      (node (ref "IC3") (pin "55") (pinfunction "PH0_55") (pintype "bidirectional"))
      (node (ref "S2") (pin "1") (pinfunction "1_1") (pintype "passive"))
    )
    (net (code "95") (name "/~{CHRG_FAULT}") (class "Default")
      (node (ref "IC2") (pin "5") (pinfunction "~{FAULT}_5") (pintype "bidirectional"))
      (node (ref "IC3") (pin "67") (pinfunction "PJ2_67") (pintype "bidirectional"))
    )
    (net (code "96") (name "/~{CHRG}") (class "Default")
      (node (ref "IC2") (pin "4") (pinfunction "~{CHRG}_4") (pintype "bidirectional"))
      (node (ref "IC3") (pin "68") (pinfunction "PJ3_68") (pintype "bidirectional"))
    )
    (net (code "97") (name "/~{EN232_1}") (class "Default")
      (node (ref "IC1") (pin "1") (pinfunction "~{EN}_1") (pintype "input"))
      (node (ref "IC19") (pin "1") (pinfunction "I_1") (pintype "input"))
      (node (ref "IC3") (pin "69") (pinfunction "PJ4_69") (pintype "bidirectional"))
    )
    (net (code "98") (name "/~{EN232_2}") (class "Default")
      (node (ref "IC19") (pin "3") (pinfunction "I_3") (pintype "input"))
      (node (ref "IC3") (pin "70") (pinfunction "PJ5_70") (pintype "bidirectional"))
      (node (ref "IC7") (pin "1") (pinfunction "~{EN}_1") (pintype "input"))
    )
    (net (code "99") (name "/~{EN232_3}") (class "Default")
      (node (ref "IC11") (pin "1") (pinfunction "~{EN}_1") (pintype "input"))
      (node (ref "IC19") (pin "5") (pinfunction "I_5") (pintype "input"))
      (node (ref "IC3") (pin "71") (pinfunction "PJ6_71") (pintype "bidirectional"))
    )
    (net (code "100") (name "/~{EN232_4}") (class "Default")
      (node (ref "IC15") (pin "1") (pinfunction "~{EN}_1") (pintype "input"))
      (node (ref "IC19") (pin "9") (pinfunction "I_9") (pintype "input"))
      (node (ref "IC3") (pin "72") (pinfunction "PJ7_72") (pintype "bidirectional"))
    )
    (net (code "101") (name "GND") (class "Default")
      (node (ref "C10") (pin "2") (pinfunction "2_2") (pintype "passive"))
      (node (ref "C11") (pin "2") (pinfunction "2_2") (pintype "passive"))
      (node (ref "C12") (pin "2") (pinfunction "2_2") (pintype "passive"))
      (node (ref "C14") (pin "2") (pinfunction "2_2") (pintype "passive"))
      (node (ref "C15") (pin "-") (pinfunction "-_-") (pintype "passive"))
      (node (ref "C18") (pin "2") (pinfunction "2_2") (pintype "passive"))
      (node (ref "C19") (pin "1") (pinfunction "1_1") (pintype "passive"))
      (node (ref "C20") (pin "2") (pinfunction "2_2") (pintype "passive"))
      (node (ref "C21") (pin "-") (pinfunction "-_-") (pintype "passive"))
      (node (ref "C22") (pin "-") (pinfunction "-_-") (pintype "passive"))
      (node (ref "C25") (pin "2") (pinfunction "2_2") (pintype "passive"))
      (node (ref "C26") (pin "1") (pinfunction "1_1") (pintype "passive"))
      (node (ref "C27") (pin "2") (pinfunction "2_2") (pintype "passive"))
      (node (ref "C28") (pin "-") (pinfunction "-_-") (pintype "passive"))
      (node (ref "C29") (pin "-") (pinfunction "-_-") (pintype "passive"))
      (node (ref "C32") (pin "2") (pinfunction "2_2") (pintype "passive"))
      (node (ref "C33") (pin "1") (pinfunction "1_1") (pintype "passive"))
      (node (ref "C34") (pin "2") (pinfunction "2_2") (pintype "passive"))
      (node (ref "C37") (pin "2") (pinfunction "2_2") (pintype "passive"))
      (node (ref "C4") (pin "2") (pinfunction "2_2") (pintype "passive"))
      (node (ref "C41") (pin "2") (pinfunction "2_2") (pintype "passive"))
      (node (ref "C43") (pin "2") (pinfunction "2_2") (pintype "passive"))
      (node (ref "C44") (pin "2") (pinfunction "2_2") (pintype "passive"))
      (node (ref "C45") (pin "2") (pinfunction "2_2") (pintype "passive"))
      (node (ref "C46") (pin "2") (pinfunction "2_2") (pintype "passive"))
      (node (ref "C47") (pin "2") (pinfunction "2_2") (pintype "passive"))
      (node (ref "C48") (pin "2") (pinfunction "2_2") (pintype "passive"))
      (node (ref "C5") (pin "1") (pinfunction "1_1") (pintype "passive"))
      (node (ref "C6") (pin "2") (pinfunction "2_2") (pintype "passive"))
      (node (ref "C7") (pin "2") (pinfunction "2_2") (pintype "passive"))
      (node (ref "C8") (pin "-") (pinfunction "-_-") (pintype "passive"))
      (node (ref "C9") (pin "2") (pinfunction "2_2") (pintype "passive"))
      (node (ref "D1") (pin "1") (pinfunction "A_1") (pintype "passive"))
      (node (ref "D10") (pin "A") (pinfunction "A_A") (pintype "passive"))
      (node (ref "D11") (pin "A") (pinfunction "A_A") (pintype "passive"))
      (node (ref "D2") (pin "1") (pinfunction "A_1") (pintype "passive"))
      (node (ref "D3") (pin "1") (pinfunction "A_1") (pintype "passive"))
      (node (ref "D4") (pin "1") (pinfunction "A_1") (pintype "passive"))
      (node (ref "D5") (pin "A") (pinfunction "A_A") (pintype "passive"))
      (node (ref "D6") (pin "1") (pinfunction "A_1") (pintype "passive"))
      (node (ref "D7") (pin "1") (pinfunction "A_1") (pintype "passive"))
      (node (ref "D8") (pin "1") (pinfunction "A_1") (pintype "passive"))
      (node (ref "IC1") (pin "14") (pinfunction "GND_14") (pintype "power_in"))
      (node (ref "IC10") (pin "2") (pinfunction "GND_2") (pintype "power_in"))
      (node (ref "IC11") (pin "14") (pinfunction "GND_14") (pintype "power_in"))
      (node (ref "IC12") (pin "4") (pinfunction "GND_4") (pintype "power_in"))
      (node (ref "IC13") (pin "2") (pinfunction "GND_2") (pintype "power_in"))
      (node (ref "IC14") (pin "2") (pinfunction "GND_2") (pintype "power_in"))
      (node (ref "IC15") (pin "14") (pinfunction "GND_14") (pintype "power_in"))
      (node (ref "IC17") (pin "2") (pinfunction "GND_2") (pintype "power_in"))
      (node (ref "IC18") (pin "2") (pinfunction "GND_2") (pintype "power_in"))
      (node (ref "IC19") (pin "11") (pinfunction "I_11") (pintype "input"))
      (node (ref "IC19") (pin "13") (pinfunction "I_13") (pintype "input"))
      (node (ref "IC19") (pin "7") (pinfunction "GND_7") (pintype "power_in"))
      (node (ref "IC2") (pin "13") (pinfunction "GND_13") (pintype "power_in"))
      (node (ref "IC20") (pin "4") (pinfunction "SD_4") (pintype "input"))
      (node (ref "IC20") (pin "5") (pinfunction "GND_5") (pintype "power_in"))
      (node (ref "IC20") (pin "6") (pinfunction "GND1_6") (pintype "input"))
      (node (ref "IC20") (pin "7") (pinfunction "GND2_7") (pintype "passive"))
      (node (ref "IC20") (pin "8") (pinfunction "GND3_8") (pintype "power_in"))
      (node (ref "IC24") (pin "4") (pinfunction "SD_4") (pintype "input"))
      (node (ref "IC24") (pin "5") (pinfunction "GND_5") (pintype "power_in"))
      (node (ref "IC24") (pin "6") (pinfunction "GND1_6") (pintype "input"))
      (node (ref "IC24") (pin "7") (pinfunction "GND2_7") (pintype "passive"))
      (node (ref "IC24") (pin "8") (pinfunction "GND3_8") (pintype "power_in"))
      (node (ref "IC3") (pin "13") (pinfunction "GND1_13") (pintype "power_in"))
      (node (ref "IC3") (pin "23") (pinfunction "GND2_23") (pintype "power_in"))
      (node (ref "IC3") (pin "3") (pinfunction "GND_3") (pintype "power_in"))
      (node (ref "IC3") (pin "33") (pinfunction "GND3_33") (pintype "power_in"))
      (node (ref "IC3") (pin "43") (pinfunction "GND4_43") (pintype "power_in"))
      (node (ref "IC3") (pin "53") (pinfunction "GND5_53") (pintype "power_in"))
      (node (ref "IC3") (pin "63") (pinfunction "GND6_63") (pintype "power_in"))
      (node (ref "IC3") (pin "73") (pinfunction "GND7_73") (pintype "power_in"))
      (node (ref "IC3") (pin "84") (pinfunction "GND8_84") (pintype "power_in"))
      (node (ref "IC3") (pin "93") (pinfunction "GND9_93") (pintype "power_in"))
      (node (ref "IC4") (pin "1") (pinfunction "GND_1") (pintype "input"))
      (node (ref "IC4") (pin "10") (pinfunction "GND1_10") (pintype "input"))
      (node (ref "IC5") (pin "2") (pinfunction "GND_2") (pintype "power_in"))
      (node (ref "IC6") (pin "2") (pinfunction "GND_2") (pintype "power_in"))
      (node (ref "IC7") (pin "14") (pinfunction "GND_14") (pintype "power_in"))
      (node (ref "IC8") (pin "4") (pinfunction "GND_4") (pintype "power_in"))
      (node (ref "IC9") (pin "2") (pinfunction "GND_2") (pintype "power_in"))
      (node (ref "ISP1") (pin "6") (pinfunction "6_6") (pintype "passive"))
      (node (ref "LED4") (pin "C") (pinfunction "C_C") (pintype "passive"))
      (node (ref "R23") (pin "1") (pinfunction "1_1") (pintype "passive"))
      (node (ref "R24") (pin "1") (pinfunction "1_1") (pintype "passive"))
      (node (ref "R25") (pin "1") (pinfunction "1_1") (pintype "passive"))
      (node (ref "R26") (pin "1") (pinfunction "1_1") (pintype "passive"))
      (node (ref "R27") (pin "1") (pinfunction "1_1") (pintype "passive"))
      (node (ref "R30") (pin "1") (pinfunction "1_1") (pintype "passive"))
      (node (ref "S1") (pin "2") (pinfunction "2_2") (pintype "passive"))
      (node (ref "S2") (pin "2") (pinfunction "2_2") (pintype "passive"))
      (node (ref "T1") (pin "1") (pinfunction "C_1") (pintype "passive"))
      (node (ref "U1") (pin "1") (pinfunction "GND_1") (pintype "bidirectional"))
      (node (ref "U1") (pin "12") (pinfunction "GND1_12") (pintype "bidirectional"))
      (node (ref "U1") (pin "25") (pinfunction "GND2_25") (pintype "bidirectional"))
      (node (ref "U1") (pin "27") (pinfunction "GND3_27") (pintype "bidirectional"))
      (node (ref "U1") (pin "28") (pinfunction "GND4_28") (pintype "bidirectional"))
      (node (ref "U1") (pin "29") (pinfunction "GND5_29") (pintype "bidirectional"))
      (node (ref "U2") (pin "4") (pinfunction "GND_4") (pintype "bidirectional"))
      (node (ref "X12") (pin "2") (pinfunction "S_2") (pintype "passive"))
      (node (ref "X14") (pin "P$1") (pinfunction "S_P$1") (pintype "passive"))
      (node (ref "X17") (pin "2") (pinfunction "S_2") (pintype "passive"))
      (node (ref "X3") (pin "7") (pinfunction "S_7") (pintype "passive"))
      (node (ref "X5") (pin "7") (pinfunction "S_7") (pintype "passive"))
      (node (ref "X6") (pin "7") (pinfunction "S_7") (pintype "passive"))
      (node (ref "X7") (pin "7") (pinfunction "S_7") (pintype "passive"))
      (node (ref "X8") (pin "3") (pinfunction "S_3") (pintype "passive"))
      (node (ref "X9") (pin "3") (pinfunction "S_3") (pintype "passive"))
    )
    (net (code "102") (name "Net-(IC1A-C1+)") (class "Default")
      (node (ref "C2") (pin "1") (pinfunction "1_1") (pintype "passive"))
      (node (ref "IC1") (pin "2") (pinfunction "C1+_2") (pintype "passive"))
    )
    (net (code "103") (name "Net-(IC1A-C1-)") (class "Default")
      (node (ref "C2") (pin "2") (pinfunction "2_2") (pintype "passive"))
      (node (ref "IC1") (pin "4") (pinfunction "C1-_4") (pintype "passive"))
    )
    (net (code "104") (name "Net-(IC1A-C2+)") (class "Default")
      (node (ref "C3") (pin "1") (pinfunction "1_1") (pintype "passive"))
      (node (ref "IC1") (pin "5") (pinfunction "C2+_5") (pintype "passive"))
    )
    (net (code "105") (name "Net-(IC1A-C2-)") (class "Default")
      (node (ref "C3") (pin "2") (pinfunction "2_2") (pintype "passive"))
      (node (ref "IC1") (pin "6") (pinfunction "C2-_6") (pintype "passive"))
    )
    (net (code "106") (name "Net-(IC1A-V+)") (class "Default")
      (node (ref "C4") (pin "1") (pinfunction "1_1") (pintype "passive"))
      (node (ref "IC1") (pin "3") (pinfunction "V+_3") (pintype "passive"))
    )
    (net (code "107") (name "Net-(IC1A-V-)") (class "Default")
      (node (ref "C5") (pin "2") (pinfunction "2_2") (pintype "passive"))
      (node (ref "IC1") (pin "7") (pinfunction "V-_7") (pintype "passive"))
    )
    (net (code "108") (name "Net-(IC2-BOOST)") (class "Default")
      (node (ref "C42") (pin "2") (pinfunction "2_2") (pintype "passive"))
      (node (ref "D9") (pin "C") (pinfunction "C_C") (pintype "passive"))
      (node (ref "IC2") (pin "11") (pinfunction "BOOST_11") (pintype "output"))
    )
    (net (code "109") (name "Net-(IC2-SW)") (class "Default")
      (node (ref "C42") (pin "1") (pinfunction "1_1") (pintype "passive"))
      (node (ref "D10") (pin "C") (pinfunction "C_C") (pintype "passive"))
      (node (ref "IC2") (pin "12") (pinfunction "SW_12") (pintype "input"))
      (node (ref "L5") (pin "1") (pinfunction "1_1") (pintype "passive"))
    )
    (net (code "110") (name "Net-(IC2-TIMER)") (class "Default")
      (node (ref "C41") (pin "1") (pinfunction "1_1") (pintype "passive"))
      (node (ref "IC2") (pin "6") (pinfunction "TIMER_6") (pintype "bidirectional"))
    )
    (net (code "111") (name "Net-(IC2-VFB)") (class "Default")
      (node (ref "IC2") (pin "7") (pinfunction "VFB_7") (pintype "bidirectional"))
      (node (ref "R22") (pin "1") (pinfunction "1_1") (pintype "passive"))
      (node (ref "R24") (pin "2") (pinfunction "2_2") (pintype "passive"))
    )
    (net (code "112") (name "Net-(IC2-VIN)") (class "Default")
      (node (ref "C29") (pin "+") (pinfunction "+_+") (pintype "passive"))
      (node (ref "C7") (pin "1") (pinfunction "1_1") (pintype "passive"))
      (node (ref "D12") (pin "C") (pinfunction "C_C") (pintype "passive"))
      (node (ref "IC2") (pin "1") (pinfunction "VIN_1") (pintype "power_in"))
      (node (ref "IC2") (pin "2") (pinfunction "VREG_2") (pintype "input"))
      (node (ref "IC2") (pin "3") (pinfunction "~{SHDN}_3") (pintype "bidirectional"))
    )
    (net (code "113") (name "Net-(IC3-PDI_DATA)") (class "Default")
      (node (ref "IC3") (pin "89") (pinfunction "PDI_DATA_89") (pintype "bidirectional"))
      (node (ref "ISP1") (pin "1") (pinfunction "1_1") (pintype "passive"))
    )
    (net (code "114") (name "Net-(IC3-~{RESET}{slash}PDI_CLK)") (class "Default")
      (node (ref "IC3") (pin "90") (pinfunction "~{RESET}/PDI_CLK_90") (pintype "input"))
      (node (ref "ISP1") (pin "5") (pinfunction "5_5") (pintype "passive"))
      (node (ref "R2") (pin "1") (pinfunction "1_1") (pintype "passive"))
    )
    (net (code "115") (name "Net-(IC4-DS1)") (class "Default")
      (node (ref "IC4") (pin "19") (pinfunction "DS1_19") (pintype "output"))
      (node (ref "R8") (pin "1") (pinfunction "1_1") (pintype "passive"))
      (node (ref "T2") (pin "2") (pinfunction "D_2") (pintype "passive"))
    )
    (net (code "116") (name "Net-(IC4-DS2)") (class "Default")
      (node (ref "IC4") (pin "17") (pinfunction "DS2_17") (pintype "input"))
      (node (ref "R9") (pin "1") (pinfunction "1_1") (pintype "passive"))
      (node (ref "T3") (pin "2") (pinfunction "D_2") (pintype "passive"))
    )
    (net (code "117") (name "Net-(IC4-DS3)") (class "Default")
      (node (ref "IC4") (pin "15") (pinfunction "DS3_15") (pintype "output"))
      (node (ref "R10") (pin "1") (pinfunction "1_1") (pintype "passive"))
      (node (ref "T4") (pin "2") (pinfunction "D_2") (pintype "passive"))
    )
    (net (code "118") (name "Net-(IC4-DS4)") (class "Default")
      (node (ref "IC4") (pin "13") (pinfunction "DS4_13") (pintype "output"))
      (node (ref "R11") (pin "1") (pinfunction "1_1") (pintype "passive"))
      (node (ref "T5") (pin "2") (pinfunction "D_2") (pintype "passive"))
    )
    (net (code "119") (name "Net-(IC4-G1)") (class "Default")
      (node (ref "IC4") (pin "18") (pinfunction "G1_18") (pintype "output"))
      (node (ref "T2") (pin "1") (pinfunction "G_1") (pintype "passive"))
    )
    (net (code "120") (name "Net-(IC4-G2)") (class "Default")
      (node (ref "IC4") (pin "16") (pinfunction "G2_16") (pintype "output"))
      (node (ref "T3") (pin "1") (pinfunction "G_1") (pintype "passive"))
    )
    (net (code "121") (name "Net-(IC4-G3)") (class "Default")
      (node (ref "IC4") (pin "14") (pinfunction "G3_14") (pintype "input"))
      (node (ref "T4") (pin "1") (pinfunction "G_1") (pintype "passive"))
    )
    (net (code "122") (name "Net-(IC4-G4)") (class "Default")
      (node (ref "IC4") (pin "12") (pinfunction "G4_12") (pintype "output"))
      (node (ref "T5") (pin "1") (pinfunction "G_1") (pintype "passive"))
    )
    (net (code "123") (name "Net-(IC7A-C1+)") (class "Default")
      (node (ref "C16") (pin "1") (pinfunction "1_1") (pintype "passive"))
      (node (ref "IC7") (pin "2") (pinfunction "C1+_2") (pintype "passive"))
    )
    (net (code "124") (name "Net-(IC7A-C1-)") (class "Default")
      (node (ref "C16") (pin "2") (pinfunction "2_2") (pintype "passive"))
      (node (ref "IC7") (pin "4") (pinfunction "C1-_4") (pintype "passive"))
    )
    (net (code "125") (name "Net-(IC7A-C2+)") (class "Default")
      (node (ref "C17") (pin "1") (pinfunction "1_1") (pintype "passive"))
      (node (ref "IC7") (pin "5") (pinfunction "C2+_5") (pintype "passive"))
    )
    (net (code "126") (name "Net-(IC7A-C2-)") (class "Default")
      (node (ref "C17") (pin "2") (pinfunction "2_2") (pintype "passive"))
      (node (ref "IC7") (pin "6") (pinfunction "C2-_6") (pintype "passive"))
    )
    (net (code "127") (name "Net-(IC7A-V+)") (class "Default")
      (node (ref "C18") (pin "1") (pinfunction "1_1") (pintype "passive"))
      (node (ref "IC7") (pin "3") (pinfunction "V+_3") (pintype "passive"))
    )
    (net (code "128") (name "Net-(IC7A-V-)") (class "Default")
      (node (ref "C19") (pin "2") (pinfunction "2_2") (pintype "passive"))
      (node (ref "IC7") (pin "7") (pinfunction "V-_7") (pintype "passive"))
    )
    (net (code "129") (name "Net-(IC8-R_OS)") (class "Default")
      (node (ref "IC8") (pin "5") (pinfunction "R_OS_5") (pintype "input"))
      (node (ref "R26") (pin "2") (pinfunction "2_2") (pintype "passive"))
    )
    (net (code "130") (name "Net-(IC11A-C1+)") (class "Default")
      (node (ref "C23") (pin "1") (pinfunction "1_1") (pintype "passive"))
      (node (ref "IC11") (pin "2") (pinfunction "C1+_2") (pintype "passive"))
    )
    (net (code "131") (name "Net-(IC11A-C1-)") (class "Default")
      (node (ref "C23") (pin "2") (pinfunction "2_2") (pintype "passive"))
      (node (ref "IC11") (pin "4") (pinfunction "C1-_4") (pintype "passive"))
    )
    (net (code "132") (name "Net-(IC11A-C2+)") (class "Default")
      (node (ref "C24") (pin "1") (pinfunction "1_1") (pintype "passive"))
      (node (ref "IC11") (pin "5") (pinfunction "C2+_5") (pintype "passive"))
    )
    (net (code "133") (name "Net-(IC11A-C2-)") (class "Default")
      (node (ref "C24") (pin "2") (pinfunction "2_2") (pintype "passive"))
      (node (ref "IC11") (pin "6") (pinfunction "C2-_6") (pintype "passive"))
    )
    (net (code "134") (name "Net-(IC11A-V+)") (class "Default")
      (node (ref "C25") (pin "1") (pinfunction "1_1") (pintype "passive"))
      (node (ref "IC11") (pin "3") (pinfunction "V+_3") (pintype "passive"))
    )
    (net (code "135") (name "Net-(IC11A-V-)") (class "Default")
      (node (ref "C26") (pin "2") (pinfunction "2_2") (pintype "passive"))
      (node (ref "IC11") (pin "7") (pinfunction "V-_7") (pintype "passive"))
    )
    (net (code "136") (name "Net-(IC12-R_OS)") (class "Default")
      (node (ref "IC12") (pin "5") (pinfunction "R_OS_5") (pintype "input"))
      (node (ref "R27") (pin "2") (pinfunction "2_2") (pintype "passive"))
    )
    (net (code "137") (name "Net-(IC15A-C1+)") (class "Default")
      (node (ref "C30") (pin "1") (pinfunction "1_1") (pintype "passive"))
      (node (ref "IC15") (pin "2") (pinfunction "C1+_2") (pintype "passive"))
    )
    (net (code "138") (name "Net-(IC15A-C1-)") (class "Default")
      (node (ref "C30") (pin "2") (pinfunction "2_2") (pintype "passive"))
      (node (ref "IC15") (pin "4") (pinfunction "C1-_4") (pintype "passive"))
    )
    (net (code "139") (name "Net-(IC15A-C2+)") (class "Default")
      (node (ref "C31") (pin "1") (pinfunction "1_1") (pintype "passive"))
      (node (ref "IC15") (pin "5") (pinfunction "C2+_5") (pintype "passive"))
    )
    (net (code "140") (name "Net-(IC15A-C2-)") (class "Default")
      (node (ref "C31") (pin "2") (pinfunction "2_2") (pintype "passive"))
      (node (ref "IC15") (pin "6") (pinfunction "C2-_6") (pintype "passive"))
    )
    (net (code "141") (name "Net-(IC15A-V+)") (class "Default")
      (node (ref "C32") (pin "1") (pinfunction "1_1") (pintype "passive"))
      (node (ref "IC15") (pin "3") (pinfunction "V+_3") (pintype "passive"))
    )
    (net (code "142") (name "Net-(IC15A-V-)") (class "Default")
      (node (ref "C33") (pin "2") (pinfunction "2_2") (pintype "passive"))
      (node (ref "IC15") (pin "7") (pinfunction "V-_7") (pintype "passive"))
    )
    (net (code "143") (name "Net-(IC20-OUT)") (class "Default")
      (node (ref "D5") (pin "C") (pinfunction "C_C") (pintype "passive"))
      (node (ref "IC20") (pin "2") (pinfunction "OUT_2") (pintype "output"))
      (node (ref "L4") (pin "1") (pinfunction "1_1") (pintype "passive"))
    )
    (net (code "144") (name "Net-(IC24-OUT)") (class "Default")
      (node (ref "D11") (pin "C") (pinfunction "C_C") (pintype "passive"))
      (node (ref "IC24") (pin "2") (pinfunction "OUT_2") (pintype "output"))
      (node (ref "L6") (pin "1") (pinfunction "1_1") (pintype "passive"))
    )
    (net (code "145") (name "Net-(LED1-PadA)") (class "Default")
      (node (ref "LED1") (pin "A") (pinfunction "A_A") (pintype "passive"))
      (node (ref "R3") (pin "1") (pinfunction "1_1") (pintype "passive"))
    )
    (net (code "146") (name "Net-(LED2-PadA)") (class "Default")
      (node (ref "LED2") (pin "A") (pinfunction "A_A") (pintype "passive"))
      (node (ref "R7") (pin "1") (pinfunction "1_1") (pintype "passive"))
    )
    (net (code "147") (name "Net-(LED3-PadA)") (class "Default")
      (node (ref "LED3") (pin "A") (pinfunction "A_A") (pintype "passive"))
      (node (ref "R28") (pin "1") (pinfunction "1_1") (pintype "passive"))
    )
    (net (code "148") (name "Net-(LED4-PadA)") (class "Default")
      (node (ref "LED4") (pin "A") (pinfunction "A_A") (pintype "passive"))
      (node (ref "R1") (pin "1") (pinfunction "1_1") (pintype "passive"))
    )
    (net (code "149") (name "Net-(LED6-CBLUE)") (class "Default")
      (node (ref "LED6") (pin "C@3") (pinfunction "CBLUE_C@3") (pintype "passive"))
      (node (ref "R32") (pin "2") (pinfunction "2_2") (pintype "passive"))
    )
    (net (code "150") (name "Net-(LED6-CGREEN)") (class "Default")
      (node (ref "LED6") (pin "C@4") (pinfunction "CGREEN_C@4") (pintype "passive"))
      (node (ref "R33") (pin "2") (pinfunction "2_2") (pintype "passive"))
    )
    (net (code "151") (name "Net-(LED6-CRED)") (class "Default")
      (node (ref "LED6") (pin "C@1") (pinfunction "CRED_C@1") (pintype "passive"))
      (node (ref "R31") (pin "2") (pinfunction "2_2") (pintype "passive"))
    )
    (net (code "152") (name "Net-(Q1-G)") (class "Default")
      (node (ref "C13") (pin "2") (pinfunction "2_2") (pintype "passive"))
      (node (ref "Q1") (pin "1") (pinfunction "G_1") (pintype "passive"))
      (node (ref "R4") (pin "1") (pinfunction "1_1") (pintype "passive"))
      (node (ref "R6") (pin "2") (pinfunction "2_2") (pintype "passive"))
      (node (ref "S1") (pin "1") (pinfunction "1_1") (pintype "passive"))
      (node (ref "T1") (pin "2") (pinfunction "E_2") (pintype "passive"))
    )
    (net (code "153") (name "Net-(T1-B)") (class "Default")
      (node (ref "R5") (pin "2") (pinfunction "2_2") (pintype "passive"))
      (node (ref "T1") (pin "3") (pinfunction "B_3") (pintype "passive"))
    )
    (net (code "154") (name "Net-(U1-PIO5)") (class "Default")
      (node (ref "LED2") (pin "C") (pinfunction "C_C") (pintype "passive"))
      (node (ref "U1") (pin "21") (pinfunction "PIO5_21") (pintype "bidirectional"))
    )
    (net (code "155") (name "Net-(U2-LED)") (class "Default")
      (node (ref "LED3") (pin "C") (pinfunction "C_C") (pintype "passive"))
      (node (ref "U2") (pin "1") (pinfunction "LED_1") (pintype "bidirectional"))
    )
    (net (code "156") (name "V+") (class "Default")
      (node (ref "C13") (pin "1") (pinfunction "1_1") (pintype "passive"))
      (node (ref "IC12") (pin "1") (pinfunction "VIN-_1") (pintype "passive"))
      (node (ref "Q1") (pin "2") (pinfunction "S_2") (pintype "passive"))
      (node (ref "R21") (pin "2") (pinfunction "2_2") (pintype "passive"))
      (node (ref "R4") (pin "2") (pinfunction "2_2") (pintype "passive"))
    )
    (net (code "157") (name "unconnected-(IC1A-FORCEON-Pad12)") (class "Default")
      (node (ref "IC1") (pin "12") (pinfunction "FORCEON_12") (pintype "input"))
    )
    (net (code "158") (name "unconnected-(IC1A-~{INVALID}-Pad10)") (class "Default")
      (node (ref "IC1") (pin "10") (pinfunction "~{INVALID}_10") (pintype "input"))
    )
    (net (code "159") (name "unconnected-(IC3-PA4-Pad99)") (class "Default")
      (node (ref "IC3") (pin "99") (pinfunction "PA4_99") (pintype "bidirectional"))
    )
    (net (code "160") (name "unconnected-(IC3-PA5-Pad100)") (class "Default")
      (node (ref "IC3") (pin "100") (pinfunction "PA5_100") (pintype "bidirectional"))
    )
    (net (code "161") (name "unconnected-(IC3-PA6-Pad1)") (class "Default")
      (node (ref "IC3") (pin "1") (pinfunction "PA6_1") (pintype "bidirectional"))
    )
    (net (code "162") (name "unconnected-(IC3-PA7-Pad2)") (class "Default")
      (node (ref "IC3") (pin "2") (pinfunction "PA7_2") (pintype "bidirectional"))
    )
    (net (code "163") (name "unconnected-(IC3-PF2-Pad47)") (class "Default")
      (node (ref "IC3") (pin "47") (pinfunction "PF2_47") (pintype "bidirectional"))
    )
    (net (code "164") (name "unconnected-(IC3-PF3-Pad48)") (class "Default")
      (node (ref "IC3") (pin "48") (pinfunction "PF3_48") (pintype "bidirectional"))
    )
    (net (code "165") (name "unconnected-(IC3-PH3-Pad58)") (class "Default")
      (node (ref "IC3") (pin "58") (pinfunction "PH3_58") (pintype "bidirectional"))
    )
    (net (code "166") (name "unconnected-(IC3-PH4-Pad59)") (class "Default")
      (node (ref "IC3") (pin "59") (pinfunction "PH4_59") (pintype "bidirectional"))
    )
    (net (code "167") (name "unconnected-(IC3-PH5-Pad60)") (class "Default")
      (node (ref "IC3") (pin "60") (pinfunction "PH5_60") (pintype "bidirectional"))
    )
    (net (code "168") (name "unconnected-(IC3-PH6-Pad61)") (class "Default")
      (node (ref "IC3") (pin "61") (pinfunction "PH6_61") (pintype "bidirectional"))
    )
    (net (code "169") (name "unconnected-(IC3-PH7-Pad62)") (class "Default")
      (node (ref "IC3") (pin "62") (pinfunction "PH7_62") (pintype "bidirectional"))
    )
    (net (code "170") (name "unconnected-(IC3-PJ0-Pad65)") (class "Default")
      (node (ref "IC3") (pin "65") (pinfunction "PJ0_65") (pintype "bidirectional"))
    )
    (net (code "171") (name "unconnected-(IC3-PJ1-Pad66)") (class "Default")
      (node (ref "IC3") (pin "66") (pinfunction "PJ1_66") (pintype "bidirectional"))
    )
    (net (code "172") (name "unconnected-(IC3-PQ0-Pad85)") (class "Default")
      (node (ref "IC3") (pin "85") (pinfunction "PQ0_85") (pintype "bidirectional"))
    )
    (net (code "173") (name "unconnected-(IC3-PQ1-Pad86)") (class "Default")
      (node (ref "IC3") (pin "86") (pinfunction "PQ1_86") (pintype "bidirectional"))
    )
    (net (code "174") (name "unconnected-(IC3-PQ2-Pad87)") (class "Default")
      (node (ref "IC3") (pin "87") (pinfunction "PQ2_87") (pintype "bidirectional"))
    )
    (net (code "175") (name "unconnected-(IC3-PQ3-Pad88)") (class "Default")
      (node (ref "IC3") (pin "88") (pinfunction "PQ3_88") (pintype "bidirectional"))
    )
    (net (code "176") (name "unconnected-(IC3-PR0(XT2)-Pad91)") (class "Default")
      (node (ref "IC3") (pin "91") (pinfunction "PR0(XT2)_91") (pintype "bidirectional"))
    )
    (net (code "177") (name "unconnected-(IC3-PR1(XT1)-Pad92)") (class "Default")
      (node (ref "IC3") (pin "92") (pinfunction "PR1(XT1)_92") (pintype "bidirectional"))
    )
    (net (code "178") (name "unconnected-(IC7A-FORCEON-Pad12)") (class "Default")
      (node (ref "IC7") (pin "12") (pinfunction "FORCEON_12") (pintype "input"))
    )
    (net (code "179") (name "unconnected-(IC7A-~{INVALID}-Pad10)") (class "Default")
      (node (ref "IC7") (pin "10") (pinfunction "~{INVALID}_10") (pintype "input"))
    )
    (net (code "180") (name "unconnected-(IC8-NC-Pad7)") (class "Default")
      (node (ref "IC8") (pin "7") (pinfunction "NC_7") (pintype "passive"))
    )
    (net (code "181") (name "unconnected-(IC11A-FORCEON-Pad12)") (class "Default")
      (node (ref "IC11") (pin "12") (pinfunction "FORCEON_12") (pintype "input"))
    )
    (net (code "182") (name "unconnected-(IC11A-~{INVALID}-Pad10)") (class "Default")
      (node (ref "IC11") (pin "10") (pinfunction "~{INVALID}_10") (pintype "input"))
    )
    (net (code "183") (name "unconnected-(IC12-NC-Pad7)") (class "Default")
      (node (ref "IC12") (pin "7") (pinfunction "NC_7") (pintype "passive"))
    )
    (net (code "184") (name "unconnected-(IC15A-FORCEON-Pad12)") (class "Default")
      (node (ref "IC15") (pin "12") (pinfunction "FORCEON_12") (pintype "input"))
    )
    (net (code "185") (name "unconnected-(IC15A-~{INVALID}-Pad10)") (class "Default")
      (node (ref "IC15") (pin "10") (pinfunction "~{INVALID}_10") (pintype "input"))
    )
    (net (code "186") (name "unconnected-(IC19E-O-Pad10)") (class "Default")
      (node (ref "IC19") (pin "10") (pinfunction "O_10") (pintype "output"))
    )
    (net (code "187") (name "unconnected-(IC19F-O-Pad12)") (class "Default")
      (node (ref "IC19") (pin "12") (pinfunction "O_12") (pintype "output"))
    )
    (net (code "188") (name "unconnected-(T2-D2-Pad4)") (class "Default")
      (node (ref "T2") (pin "4") (pinfunction "D2_4") (pintype "passive"))
    )
    (net (code "189") (name "unconnected-(T3-D2-Pad4)") (class "Default")
      (node (ref "T3") (pin "4") (pinfunction "D2_4") (pintype "passive"))
    )
    (net (code "190") (name "unconnected-(T4-D2-Pad4)") (class "Default")
      (node (ref "T4") (pin "4") (pinfunction "D2_4") (pintype "passive"))
    )
    (net (code "191") (name "unconnected-(T5-D2-Pad4)") (class "Default")
      (node (ref "T5") (pin "4") (pinfunction "D2_4") (pintype "passive"))
    )
    (net (code "192") (name "unconnected-(U1-AIO1-Pad35)") (class "Default")
      (node (ref "U1") (pin "35") (pinfunction "AIO1_35") (pintype "bidirectional"))
    )
    (net (code "193") (name "unconnected-(U1-AIO2-Pad30)") (class "Default")
      (node (ref "U1") (pin "30") (pinfunction "AIO2_30") (pintype "bidirectional"))
    )
    (net (code "194") (name "unconnected-(U1-NC-Pad26)") (class "Default")
      (node (ref "U1") (pin "26") (pinfunction "NC_26") (pintype "bidirectional"))
    )
    (net (code "195") (name "unconnected-(U1-PCMCLK-Pad7)") (class "Default")
      (node (ref "U1") (pin "7") (pinfunction "PCMCLK_7") (pintype "bidirectional"))
    )
    (net (code "196") (name "unconnected-(U1-PCMIN-Pad9)") (class "Default")
      (node (ref "U1") (pin "9") (pinfunction "PCMIN_9") (pintype "bidirectional"))
    )
    (net (code "197") (name "unconnected-(U1-PCMOUT-Pad10)") (class "Default")
      (node (ref "U1") (pin "10") (pinfunction "PCMOUT_10") (pintype "bidirectional"))
    )
    (net (code "198") (name "unconnected-(U1-PCMSYNC-Pad8)") (class "Default")
      (node (ref "U1") (pin "8") (pinfunction "PCMSYNC_8") (pintype "bidirectional"))
    )
    (net (code "199") (name "unconnected-(U1-PIO3-Pad20)") (class "Default")
      (node (ref "U1") (pin "20") (pinfunction "PIO3_20") (pintype "bidirectional"))
    )
    (net (code "200") (name "unconnected-(U1-PIO4-Pad22)") (class "Default")
      (node (ref "U1") (pin "22") (pinfunction "PIO4_22") (pintype "bidirectional"))
    )
    (net (code "201") (name "unconnected-(U1-PIO6-Pad3)") (class "Default")
      (node (ref "U1") (pin "3") (pinfunction "PIO6_3") (pintype "bidirectional"))
    )
    (net (code "202") (name "unconnected-(U1-PIO7-Pad4)") (class "Default")
      (node (ref "U1") (pin "4") (pinfunction "PIO7_4") (pintype "bidirectional"))
    )
    (net (code "203") (name "unconnected-(U1-PIO8-Pad31)") (class "Default")
      (node (ref "U1") (pin "31") (pinfunction "PIO8_31") (pintype "bidirectional"))
    )
    (net (code "204") (name "unconnected-(U1-PIO9-Pad32)") (class "Default")
      (node (ref "U1") (pin "32") (pinfunction "PIO9_32") (pintype "bidirectional"))
    )
    (net (code "205") (name "unconnected-(U1-PIO10-Pad33)") (class "Default")
      (node (ref "U1") (pin "33") (pinfunction "PIO10_33") (pintype "bidirectional"))
    )
    (net (code "206") (name "unconnected-(U1-PIO11-Pad34)") (class "Default")
      (node (ref "U1") (pin "34") (pinfunction "PIO11_34") (pintype "bidirectional"))
    )
    (net (code "207") (name "unconnected-(U1-SPICLK-Pad6)") (class "Default")
      (node (ref "U1") (pin "6") (pinfunction "SPICLK_6") (pintype "bidirectional"))
    )
    (net (code "208") (name "unconnected-(U1-SPICSB-Pad23)") (class "Default")
      (node (ref "U1") (pin "23") (pinfunction "SPICSB_23") (pintype "bidirectional"))
    )
    (net (code "209") (name "unconnected-(U1-SPIMISO-Pad24)") (class "Default")
      (node (ref "U1") (pin "24") (pinfunction "SPIMISO_24") (pintype "bidirectional"))
    )
    (net (code "210") (name "unconnected-(U1-SPIMOSI-Pad2)") (class "Default")
      (node (ref "U1") (pin "2") (pinfunction "SPIMOSI_2") (pintype "bidirectional"))
    )
    (net (code "211") (name "unconnected-(U1-USBD+-Pad17)") (class "Default")
      (node (ref "U1") (pin "17") (pinfunction "USBD+_17") (pintype "bidirectional"))
    )
    (net (code "212") (name "unconnected-(U1-USBD--Pad18)") (class "Default")
      (node (ref "U1") (pin "18") (pinfunction "USBD-_18") (pintype "bidirectional"))
    )
    (net (code "213") (name "unconnected-(U2-VBAT-Pad2)") (class "Default")
      (node (ref "U2") (pin "2") (pinfunction "VBAT_2") (pintype "bidirectional"))
    )
    (net (code "214") (name "unconnected-(X8B-S-Pad2)") (class "Default")
      (node (ref "X8") (pin "2") (pinfunction "S_2") (pintype "passive"))
    )
    (net (code "215") (name "unconnected-(X9B-S-Pad2)") (class "Default")
      (node (ref "X9") (pin "2") (pinfunction "S_2") (pintype "passive"))
    )
  )
)
